# Embedded.net
KiCad netlist of a schematic drawn in EAGLE
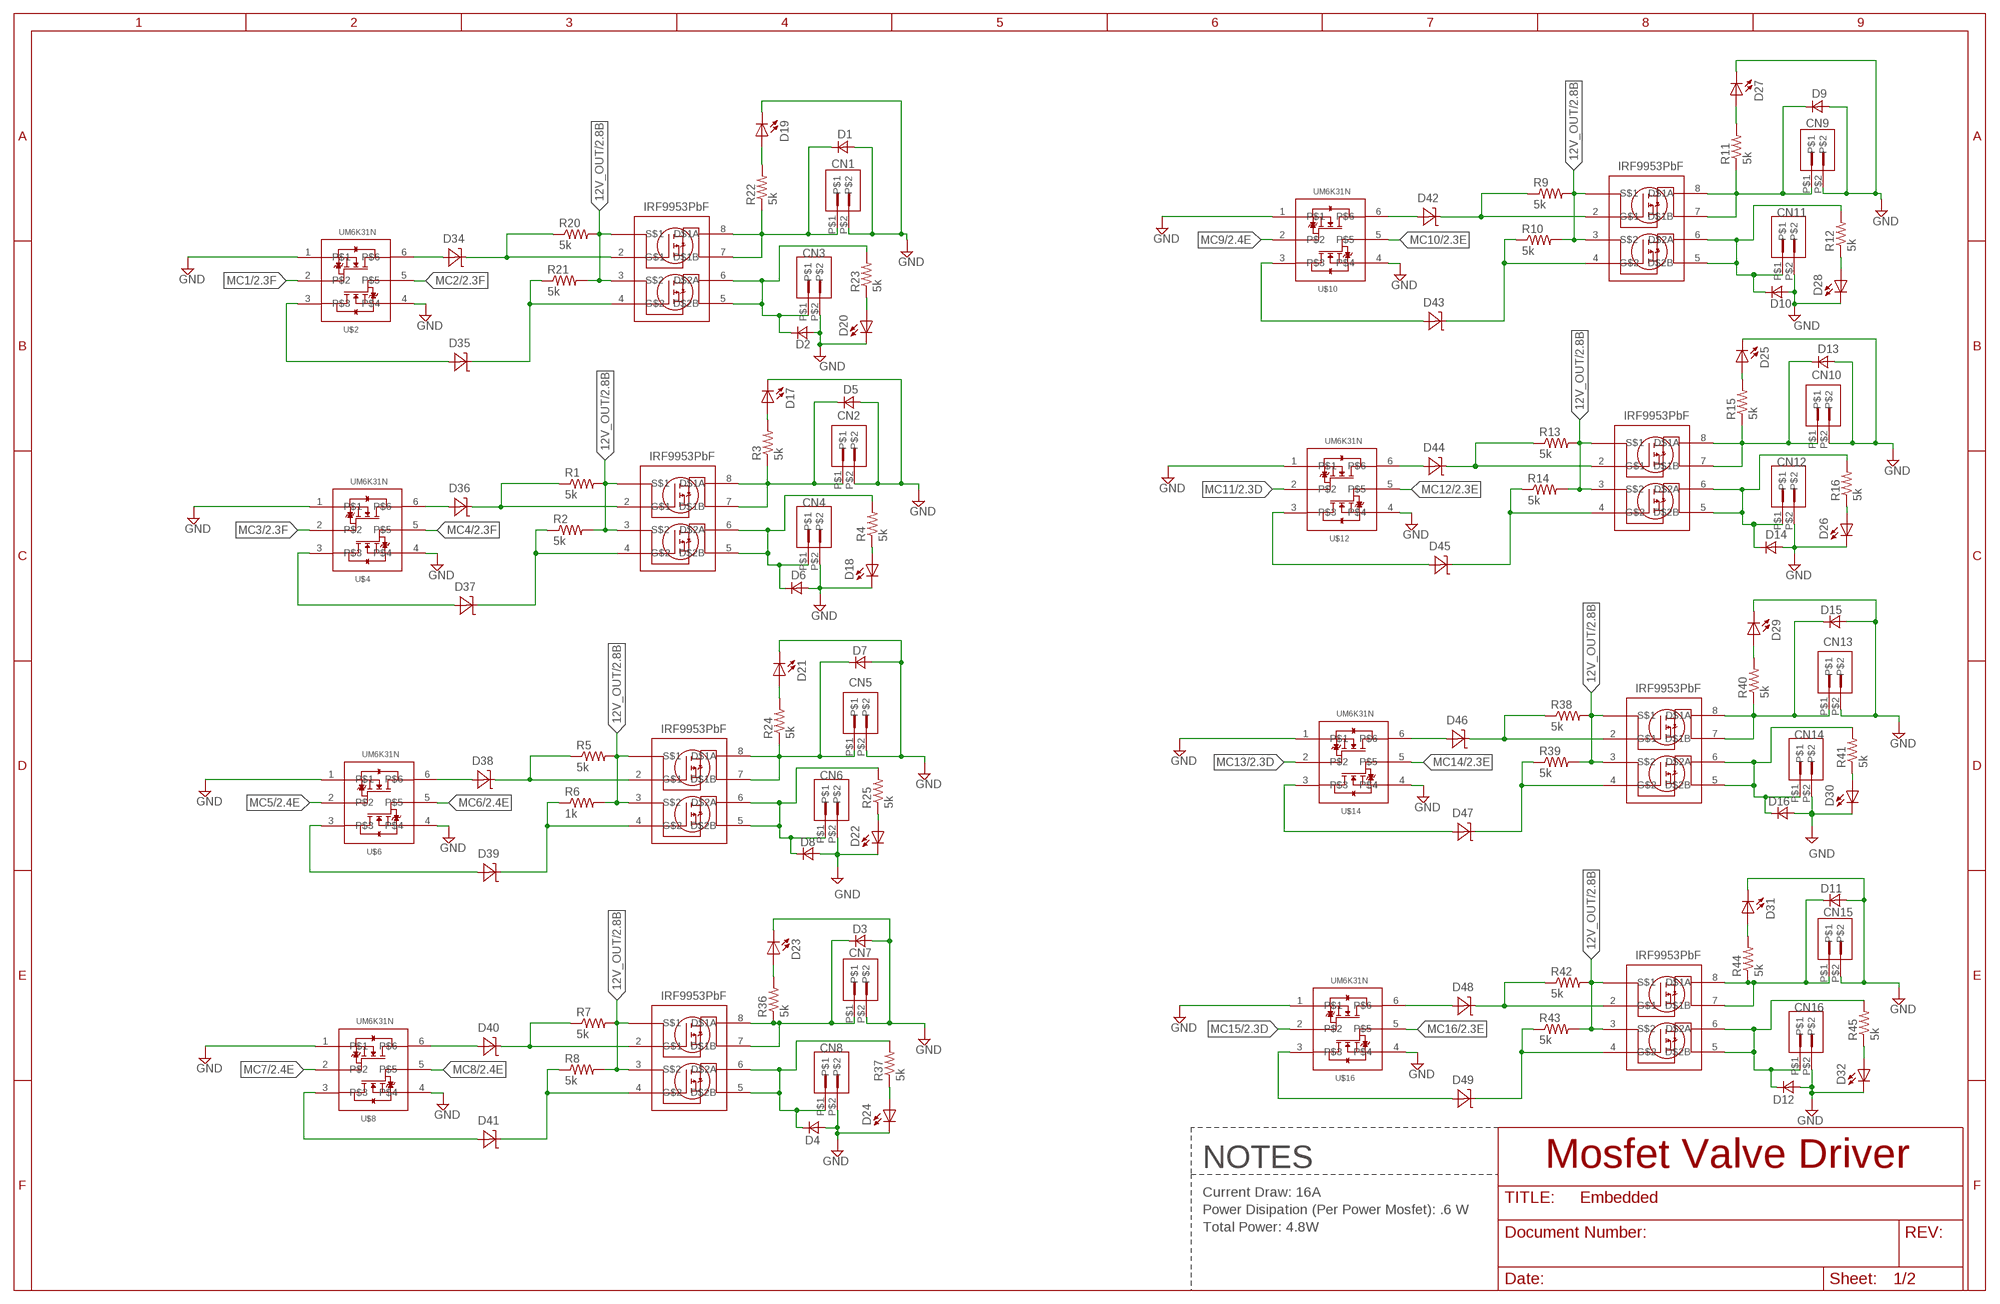
[diagram p0: schematic, sheet 1]
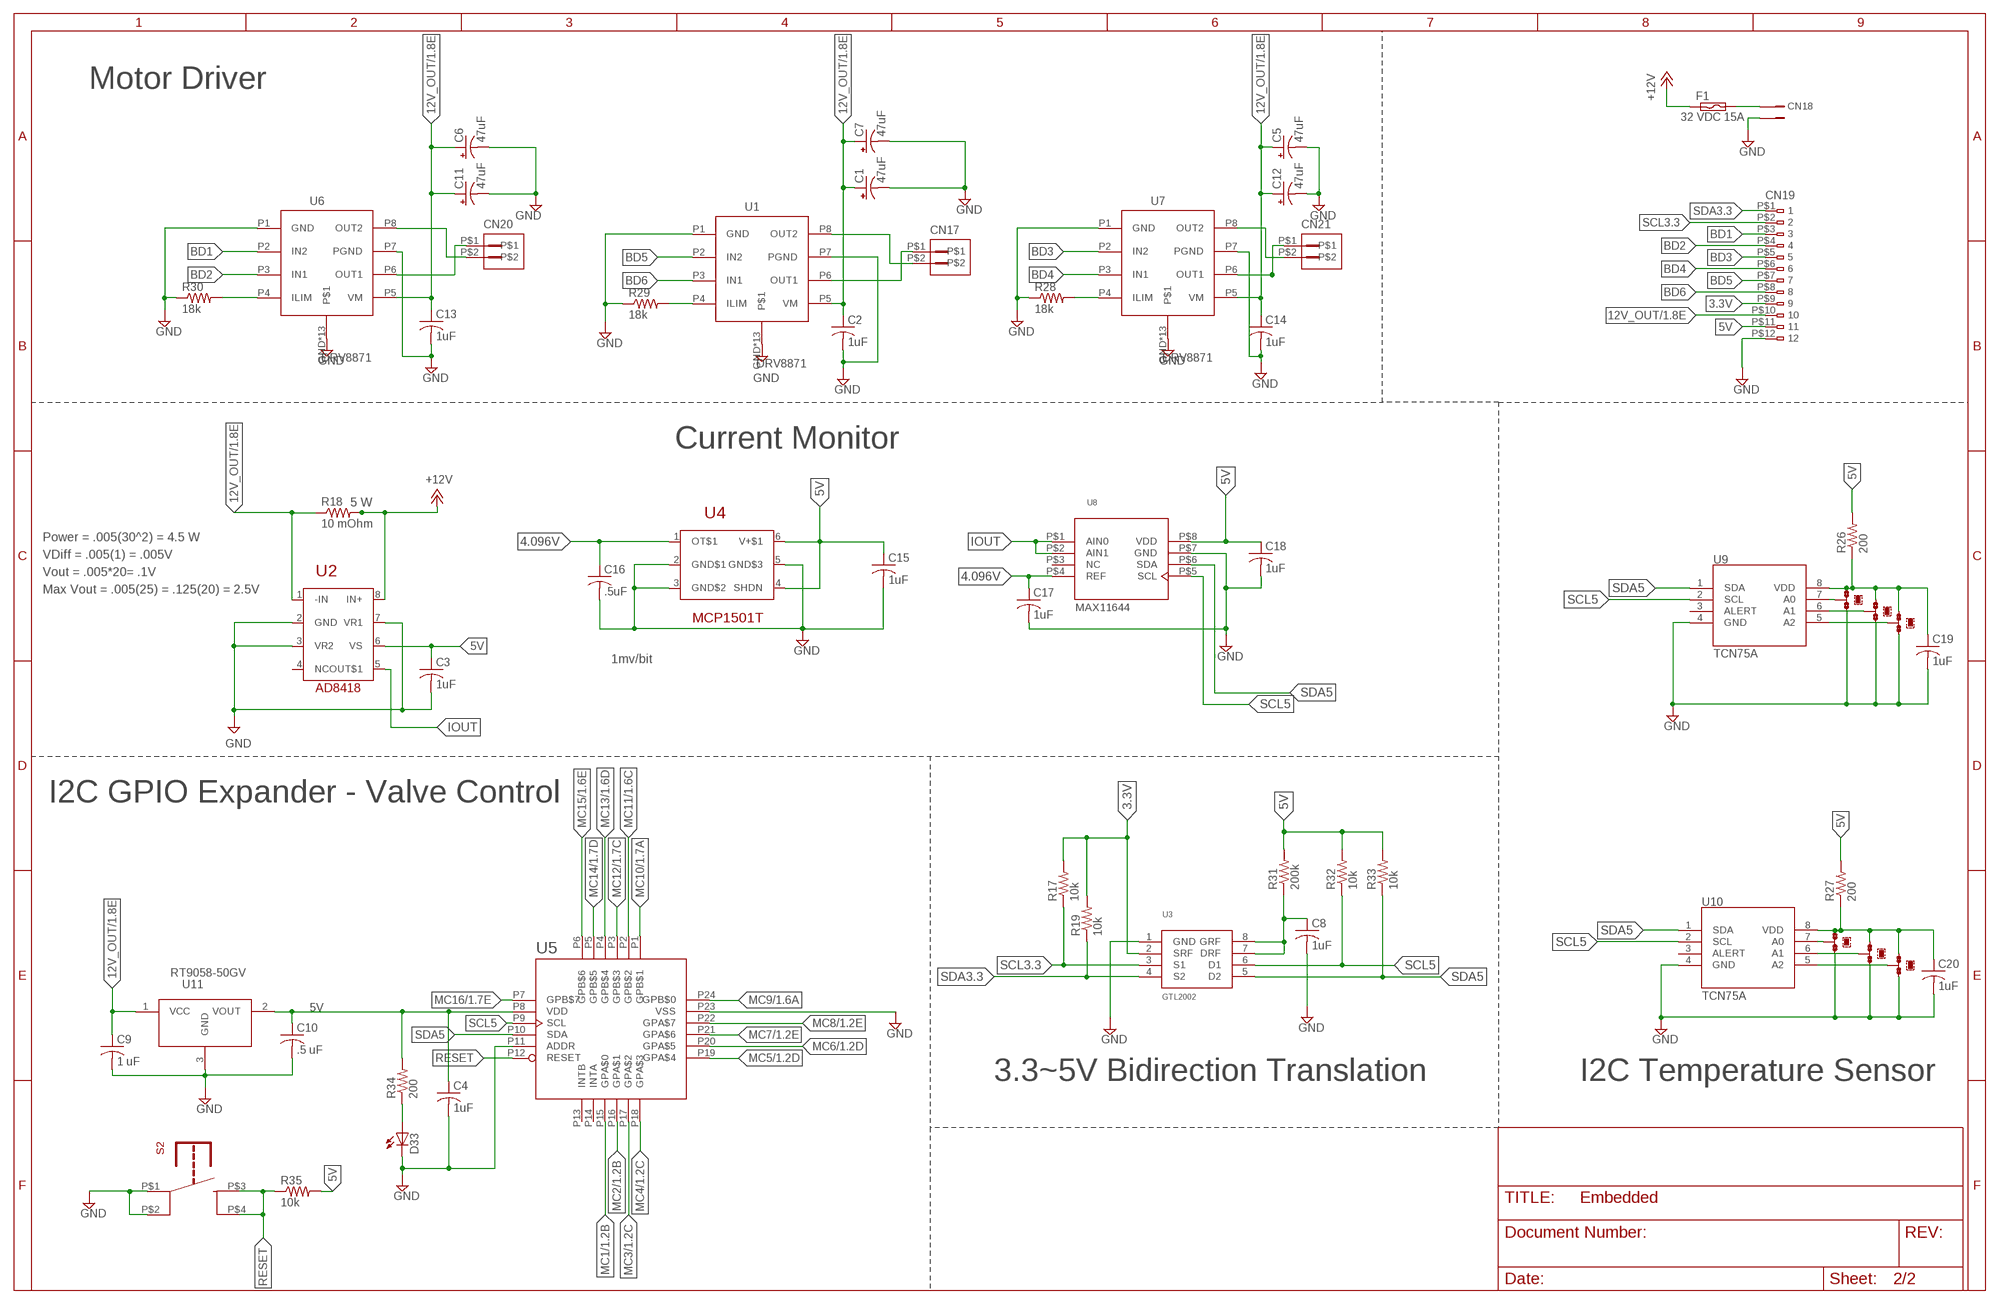
[diagram p1: schematic, sheet 2]

(export (version "E")
  (design (tool "Eeschema 10.0.6"))
  (components
    (comp (ref "CN1")
      (value "KF2510-2")
      (footprint "eagle-import:KF2540-2")
      (libsource (lib "eagle-import") (part "KF2510-2"))
    )
    (comp (ref "CN2")
      (value "KF2510-2")
      (footprint "eagle-import:KF2540-2")
      (libsource (lib "eagle-import") (part "KF2510-2"))
    )
    (comp (ref "CN3")
      (value "KF2510-2")
      (footprint "eagle-import:KF2540-2")
      (libsource (lib "eagle-import") (part "KF2510-2"))
    )
    (comp (ref "CN4")
      (value "KF2510-2")
      (footprint "eagle-import:KF2540-2")
      (libsource (lib "eagle-import") (part "KF2510-2"))
    )
    (comp (ref "CN5")
      (value "KF2510-2")
      (footprint "eagle-import:KF2540-2")
      (libsource (lib "eagle-import") (part "KF2510-2"))
    )
    (comp (ref "CN6")
      (value "KF2510-2")
      (footprint "eagle-import:KF2540-2")
      (libsource (lib "eagle-import") (part "KF2510-2"))
    )
    (comp (ref "CN7")
      (value "KF2510-2")
      (footprint "eagle-import:KF2540-2")
      (libsource (lib "eagle-import") (part "KF2510-2"))
    )
    (comp (ref "CN8")
      (value "KF2510-2")
      (footprint "eagle-import:KF2540-2")
      (libsource (lib "eagle-import") (part "KF2510-2"))
    )
    (comp (ref "CN9")
      (value "KF2510-2")
      (footprint "eagle-import:KF2540-2")
      (libsource (lib "eagle-import") (part "KF2510-2"))
    )
    (comp (ref "CN10")
      (value "KF2510-2")
      (footprint "eagle-import:KF2540-2")
      (libsource (lib "eagle-import") (part "KF2510-2"))
    )
    (comp (ref "CN11")
      (value "KF2510-2")
      (footprint "eagle-import:KF2540-2")
      (libsource (lib "eagle-import") (part "KF2510-2"))
    )
    (comp (ref "CN12")
      (value "KF2510-2")
      (footprint "eagle-import:KF2540-2")
      (libsource (lib "eagle-import") (part "KF2510-2"))
    )
    (comp (ref "CN13")
      (value "KF2510-2")
      (footprint "eagle-import:KF2540-2")
      (libsource (lib "eagle-import") (part "KF2510-2"))
    )
    (comp (ref "CN14")
      (value "KF2510-2")
      (footprint "eagle-import:KF2540-2")
      (libsource (lib "eagle-import") (part "KF2510-2"))
    )
    (comp (ref "CN15")
      (value "KF2510-2")
      (footprint "eagle-import:KF2540-2")
      (libsource (lib "eagle-import") (part "KF2510-2"))
    )
    (comp (ref "CN16")
      (value "KF2510-2")
      (footprint "eagle-import:KF2540-2")
      (libsource (lib "eagle-import") (part "KF2510-2"))
    )
    (comp (ref "D1")
      (value "RS1AL_DIODE")
      (footprint "eagle-import:DO219")
      (libsource (lib "eagle-import") (part "RS1AL_DIODE"))
    )
    (comp (ref "D2")
      (value "RS1AL_DIODE")
      (footprint "eagle-import:DO219")
      (libsource (lib "eagle-import") (part "RS1AL_DIODE"))
    )
    (comp (ref "D3")
      (value "RS1AL_DIODE")
      (footprint "eagle-import:DO219")
      (libsource (lib "eagle-import") (part "RS1AL_DIODE"))
    )
    (comp (ref "D4")
      (value "RS1AL_DIODE")
      (footprint "eagle-import:DO219")
      (libsource (lib "eagle-import") (part "RS1AL_DIODE"))
    )
    (comp (ref "D5")
      (value "RS1AL_DIODE")
      (footprint "eagle-import:DO219")
      (libsource (lib "eagle-import") (part "RS1AL_DIODE"))
    )
    (comp (ref "D6")
      (value "RS1AL_DIODE")
      (footprint "eagle-import:DO219")
      (libsource (lib "eagle-import") (part "RS1AL_DIODE"))
    )
    (comp (ref "D7")
      (value "RS1AL_DIODE")
      (footprint "eagle-import:DO219")
      (libsource (lib "eagle-import") (part "RS1AL_DIODE"))
    )
    (comp (ref "D8")
      (value "RS1AL_DIODE")
      (footprint "eagle-import:DO219")
      (libsource (lib "eagle-import") (part "RS1AL_DIODE"))
    )
    (comp (ref "D9")
      (value "RS1AL_DIODE")
      (footprint "eagle-import:DO219")
      (libsource (lib "eagle-import") (part "RS1AL_DIODE"))
    )
    (comp (ref "D10")
      (value "RS1AL_DIODE")
      (footprint "eagle-import:DO219")
      (libsource (lib "eagle-import") (part "RS1AL_DIODE"))
    )
    (comp (ref "D11")
      (value "RS1AL_DIODE")
      (footprint "eagle-import:DO219")
      (libsource (lib "eagle-import") (part "RS1AL_DIODE"))
    )
    (comp (ref "D12")
      (value "RS1AL_DIODE")
      (footprint "eagle-import:DO219")
      (libsource (lib "eagle-import") (part "RS1AL_DIODE"))
    )
    (comp (ref "D13")
      (value "RS1AL_DIODE")
      (footprint "eagle-import:DO219")
      (libsource (lib "eagle-import") (part "RS1AL_DIODE"))
    )
    (comp (ref "D14")
      (value "RS1AL_DIODE")
      (footprint "eagle-import:DO219")
      (libsource (lib "eagle-import") (part "RS1AL_DIODE"))
    )
    (comp (ref "D15")
      (value "RS1AL_DIODE")
      (footprint "eagle-import:DO219")
      (libsource (lib "eagle-import") (part "RS1AL_DIODE"))
    )
    (comp (ref "D16")
      (value "RS1AL_DIODE")
      (footprint "eagle-import:DO219")
      (libsource (lib "eagle-import") (part "RS1AL_DIODE"))
    )
    (comp (ref "D17")
      (value "1206LED")
      (footprint "eagle-import:1206")
      (libsource (lib "eagle-import") (part "1206LED"))
    )
    (comp (ref "D18")
      (value "1206LED")
      (footprint "eagle-import:1206")
      (libsource (lib "eagle-import") (part "1206LED"))
    )
    (comp (ref "D19")
      (value "1206LED")
      (footprint "eagle-import:1206")
      (libsource (lib "eagle-import") (part "1206LED"))
    )
    (comp (ref "D20")
      (value "1206LED")
      (footprint "eagle-import:1206")
      (libsource (lib "eagle-import") (part "1206LED"))
    )
    (comp (ref "D21")
      (value "1206LED")
      (footprint "eagle-import:1206")
      (libsource (lib "eagle-import") (part "1206LED"))
    )
    (comp (ref "D22")
      (value "1206LED")
      (footprint "eagle-import:1206")
      (libsource (lib "eagle-import") (part "1206LED"))
    )
    (comp (ref "D23")
      (value "1206LED")
      (footprint "eagle-import:1206")
      (libsource (lib "eagle-import") (part "1206LED"))
    )
    (comp (ref "D24")
      (value "1206LED")
      (footprint "eagle-import:1206")
      (libsource (lib "eagle-import") (part "1206LED"))
    )
    (comp (ref "D25")
      (value "1206LED")
      (footprint "eagle-import:1206")
      (libsource (lib "eagle-import") (part "1206LED"))
    )
    (comp (ref "D26")
      (value "1206LED")
      (footprint "eagle-import:1206")
      (libsource (lib "eagle-import") (part "1206LED"))
    )
    (comp (ref "D27")
      (value "1206LED")
      (footprint "eagle-import:1206")
      (libsource (lib "eagle-import") (part "1206LED"))
    )
    (comp (ref "D28")
      (value "1206LED")
      (footprint "eagle-import:1206")
      (libsource (lib "eagle-import") (part "1206LED"))
    )
    (comp (ref "D29")
      (value "1206LED")
      (footprint "eagle-import:1206")
      (libsource (lib "eagle-import") (part "1206LED"))
    )
    (comp (ref "D30")
      (value "1206LED")
      (footprint "eagle-import:1206")
      (libsource (lib "eagle-import") (part "1206LED"))
    )
    (comp (ref "D31")
      (value "1206LED")
      (footprint "eagle-import:1206")
      (libsource (lib "eagle-import") (part "1206LED"))
    )
    (comp (ref "D32")
      (value "1206LED")
      (footprint "eagle-import:1206")
      (libsource (lib "eagle-import") (part "1206LED"))
    )
    (comp (ref "D34")
      (value "6.2V")
      (footprint "eagle-import:SOD_323F")
      (libsource (lib "eagle-import") (part "MM3Z6V2B"))
    )
    (comp (ref "D35")
      (value "6.2V")
      (footprint "eagle-import:SOD_323F")
      (libsource (lib "eagle-import") (part "MM3Z6V2B"))
    )
    (comp (ref "D36")
      (value "6.2")
      (footprint "eagle-import:SOD_323F")
      (libsource (lib "eagle-import") (part "MM3Z6V2B"))
    )
    (comp (ref "D37")
      (value "6.2V")
      (footprint "eagle-import:SOD_323F")
      (libsource (lib "eagle-import") (part "MM3Z6V2B"))
    )
    (comp (ref "D38")
      (value "6.2V")
      (footprint "eagle-import:SOD_323F")
      (libsource (lib "eagle-import") (part "MM3Z6V2B"))
    )
    (comp (ref "D39")
      (value "6.2V")
      (footprint "eagle-import:SOD_323F")
      (libsource (lib "eagle-import") (part "MM3Z6V2B"))
    )
    (comp (ref "D40")
      (value "6.2V")
      (footprint "eagle-import:SOD_323F")
      (libsource (lib "eagle-import") (part "MM3Z6V2B"))
    )
    (comp (ref "D41")
      (value "6.2V")
      (footprint "eagle-import:SOD_323F")
      (libsource (lib "eagle-import") (part "MM3Z6V2B"))
    )
    (comp (ref "D42")
      (value "6.2V")
      (footprint "eagle-import:SOD_323F")
      (libsource (lib "eagle-import") (part "MM3Z6V2B"))
    )
    (comp (ref "D43")
      (value "6.2V")
      (footprint "eagle-import:SOD_323F")
      (libsource (lib "eagle-import") (part "MM3Z6V2B"))
    )
    (comp (ref "D44")
      (value "6.2V")
      (footprint "eagle-import:SOD_323F")
      (libsource (lib "eagle-import") (part "MM3Z6V2B"))
    )
    (comp (ref "D45")
      (value "6.2V")
      (footprint "eagle-import:SOD_323F")
      (libsource (lib "eagle-import") (part "MM3Z6V2B"))
    )
    (comp (ref "D46")
      (value "6.2V")
      (footprint "eagle-import:SOD_323F")
      (libsource (lib "eagle-import") (part "MM3Z6V2B"))
    )
    (comp (ref "D47")
      (value "6.2V")
      (footprint "eagle-import:SOD_323F")
      (libsource (lib "eagle-import") (part "MM3Z6V2B"))
    )
    (comp (ref "D48")
      (value "6.2V")
      (footprint "eagle-import:SOD_323F")
      (libsource (lib "eagle-import") (part "MM3Z6V2B"))
    )
    (comp (ref "D49")
      (value "6.2V")
      (footprint "eagle-import:SOD_323F")
      (libsource (lib "eagle-import") (part "MM3Z6V2B"))
    )
    (comp (ref "R1")
      (value "5k")
      (footprint "eagle-import:M0805")
      (libsource (lib "eagle-import") (part "R-US_M0805"))
    )
    (comp (ref "R2")
      (value "5k")
      (footprint "eagle-import:M0805")
      (libsource (lib "eagle-import") (part "R-US_M0805"))
    )
    (comp (ref "R3")
      (value "5k")
      (footprint "eagle-import:M0805")
      (libsource (lib "eagle-import") (part "R-US_M0805"))
    )
    (comp (ref "R4")
      (value "5k")
      (footprint "eagle-import:M0805")
      (libsource (lib "eagle-import") (part "R-US_M0805"))
    )
    (comp (ref "R5")
      (value "5k")
      (footprint "eagle-import:M0805")
      (libsource (lib "eagle-import") (part "R-US_M0805"))
    )
    (comp (ref "R6")
      (value "1k")
      (footprint "eagle-import:M0805")
      (libsource (lib "eagle-import") (part "R-US_M0805"))
    )
    (comp (ref "R7")
      (value "5k")
      (footprint "eagle-import:M0805")
      (libsource (lib "eagle-import") (part "R-US_M0805"))
    )
    (comp (ref "R8")
      (value "5k")
      (footprint "eagle-import:M0805")
      (libsource (lib "eagle-import") (part "R-US_M0805"))
    )
    (comp (ref "R9")
      (value "5k")
      (footprint "eagle-import:M0805")
      (libsource (lib "eagle-import") (part "R-US_M0805"))
    )
    (comp (ref "R10")
      (value "5k")
      (footprint "eagle-import:M0805")
      (libsource (lib "eagle-import") (part "R-US_M0805"))
    )
    (comp (ref "R11")
      (value "5k")
      (footprint "eagle-import:M0805")
      (libsource (lib "eagle-import") (part "R-US_M0805"))
    )
    (comp (ref "R12")
      (value "5k")
      (footprint "eagle-import:M0805")
      (libsource (lib "eagle-import") (part "R-US_M0805"))
    )
    (comp (ref "R13")
      (value "5k")
      (footprint "eagle-import:M0805")
      (libsource (lib "eagle-import") (part "R-US_M0805"))
    )
    (comp (ref "R14")
      (value "5k")
      (footprint "eagle-import:M0805")
      (libsource (lib "eagle-import") (part "R-US_M0805"))
    )
    (comp (ref "R15")
      (value "5k")
      (footprint "eagle-import:M0805")
      (libsource (lib "eagle-import") (part "R-US_M0805"))
    )
    (comp (ref "R16")
      (value "5k")
      (footprint "eagle-import:M0805")
      (libsource (lib "eagle-import") (part "R-US_M0805"))
    )
    (comp (ref "R20")
      (value "5k")
      (footprint "eagle-import:M0805")
      (libsource (lib "eagle-import") (part "R-US_M0805"))
    )
    (comp (ref "R21")
      (value "5k")
      (footprint "eagle-import:M0805")
      (libsource (lib "eagle-import") (part "R-US_M0805"))
    )
    (comp (ref "R22")
      (value "5k")
      (footprint "eagle-import:M0805")
      (libsource (lib "eagle-import") (part "R-US_M0805"))
    )
    (comp (ref "R23")
      (value "5k")
      (footprint "eagle-import:M0805")
      (libsource (lib "eagle-import") (part "R-US_M0805"))
    )
    (comp (ref "R24")
      (value "5k")
      (footprint "eagle-import:M0805")
      (libsource (lib "eagle-import") (part "R-US_M0805"))
    )
    (comp (ref "R25")
      (value "5k")
      (footprint "eagle-import:M0805")
      (libsource (lib "eagle-import") (part "R-US_M0805"))
    )
    (comp (ref "R36")
      (value "5k")
      (footprint "eagle-import:M0805")
      (libsource (lib "eagle-import") (part "R-US_M0805"))
    )
    (comp (ref "R37")
      (value "5k")
      (footprint "eagle-import:M0805")
      (libsource (lib "eagle-import") (part "R-US_M0805"))
    )
    (comp (ref "R38")
      (value "5k")
      (footprint "eagle-import:M0805")
      (libsource (lib "eagle-import") (part "R-US_M0805"))
    )
    (comp (ref "R39")
      (value "5k")
      (footprint "eagle-import:M0805")
      (libsource (lib "eagle-import") (part "R-US_M0805"))
    )
    (comp (ref "R40")
      (value "5k")
      (footprint "eagle-import:M0805")
      (libsource (lib "eagle-import") (part "R-US_M0805"))
    )
    (comp (ref "R41")
      (value "5k")
      (footprint "eagle-import:M0805")
      (libsource (lib "eagle-import") (part "R-US_M0805"))
    )
    (comp (ref "R42")
      (value "5k")
      (footprint "eagle-import:M0805")
      (libsource (lib "eagle-import") (part "R-US_M0805"))
    )
    (comp (ref "R43")
      (value "5k")
      (footprint "eagle-import:M0805")
      (libsource (lib "eagle-import") (part "R-US_M0805"))
    )
    (comp (ref "R44")
      (value "5k")
      (footprint "eagle-import:M0805")
      (libsource (lib "eagle-import") (part "R-US_M0805"))
    )
    (comp (ref "R45")
      (value "5k")
      (footprint "eagle-import:M0805")
      (libsource (lib "eagle-import") (part "R-US_M0805"))
    )
    (comp (ref "U$1")
      (value "IRF9953PBF")
      (footprint "eagle-import:SO-8")
      (libsource (lib "eagle-import") (part "IRF9953PBF"))
    )
    (comp (ref "U$2")
      (value "UM6K31N")
      (footprint "eagle-import:UMT6")
      (libsource (lib "eagle-import") (part "UM6K31N"))
    )
    (comp (ref "U$3")
      (value "IRF9953PBF")
      (footprint "eagle-import:SO-8")
      (libsource (lib "eagle-import") (part "IRF9953PBF"))
    )
    (comp (ref "U$4")
      (value "UM6K31N")
      (footprint "eagle-import:UMT6")
      (libsource (lib "eagle-import") (part "UM6K31N"))
    )
    (comp (ref "U$5")
      (value "IRF9953PBF")
      (footprint "eagle-import:SO-8")
      (libsource (lib "eagle-import") (part "IRF9953PBF"))
    )
    (comp (ref "U$6")
      (value "UM6K31N")
      (footprint "eagle-import:UMT6")
      (libsource (lib "eagle-import") (part "UM6K31N"))
    )
    (comp (ref "U$7")
      (value "IRF9953PBF")
      (footprint "eagle-import:SO-8")
      (libsource (lib "eagle-import") (part "IRF9953PBF"))
    )
    (comp (ref "U$8")
      (value "UM6K31N")
      (footprint "eagle-import:UMT6")
      (libsource (lib "eagle-import") (part "UM6K31N"))
    )
    (comp (ref "U$9")
      (value "IRF9953PBF")
      (footprint "eagle-import:SO-8")
      (libsource (lib "eagle-import") (part "IRF9953PBF"))
    )
    (comp (ref "U$10")
      (value "UM6K31N")
      (footprint "eagle-import:UMT6")
      (libsource (lib "eagle-import") (part "UM6K31N"))
    )
    (comp (ref "U$11")
      (value "IRF9953PBF")
      (footprint "eagle-import:SO-8")
      (libsource (lib "eagle-import") (part "IRF9953PBF"))
    )
    (comp (ref "U$12")
      (value "UM6K31N")
      (footprint "eagle-import:UMT6")
      (libsource (lib "eagle-import") (part "UM6K31N"))
    )
    (comp (ref "U$13")
      (value "IRF9953PBF")
      (footprint "eagle-import:SO-8")
      (libsource (lib "eagle-import") (part "IRF9953PBF"))
    )
    (comp (ref "U$14")
      (value "UM6K31N")
      (footprint "eagle-import:UMT6")
      (libsource (lib "eagle-import") (part "UM6K31N"))
    )
    (comp (ref "U$15")
      (value "IRF9953PBF")
      (footprint "eagle-import:SO-8")
      (libsource (lib "eagle-import") (part "IRF9953PBF"))
    )
    (comp (ref "U$16")
      (value "UM6K31N")
      (footprint "eagle-import:UMT6")
      (libsource (lib "eagle-import") (part "UM6K31N"))
    )
    (comp (ref "C1")
      (value "47uF")
      (footprint "eagle-import:UD-6,3X7,7_NICHICON")
      (libsource (lib "eagle-import") (part "CPOL-USUD-6,3X7,7"))
    )
    (comp (ref "C2")
      (value "1uF")
      (footprint "eagle-import:C1206")
      (libsource (lib "eagle-import") (part "C-USC1206"))
    )
    (comp (ref "C3")
      (value "1uF")
      (footprint "eagle-import:C1206")
      (libsource (lib "eagle-import") (part "C-USC1206"))
    )
    (comp (ref "C4")
      (value "1uF")
      (footprint "eagle-import:C1206")
      (libsource (lib "eagle-import") (part "C-USC1206"))
    )
    (comp (ref "C5")
      (value "47uF")
      (footprint "eagle-import:UD-6,3X7,7_NICHICON")
      (libsource (lib "eagle-import") (part "CPOL-USUD-6,3X7,7"))
    )
    (comp (ref "C6")
      (value "47uF")
      (footprint "eagle-import:UD-6,3X7,7_NICHICON")
      (libsource (lib "eagle-import") (part "CPOL-USUD-6,3X7,7"))
    )
    (comp (ref "C7")
      (value "47uF")
      (footprint "eagle-import:UD-6,3X7,7_NICHICON")
      (libsource (lib "eagle-import") (part "CPOL-USUD-6,3X7,7"))
    )
    (comp (ref "C8")
      (value "1uF")
      (footprint "eagle-import:C1206")
      (libsource (lib "eagle-import") (part "C-USC1206"))
    )
    (comp (ref "C9")
      (value "1 uF")
      (footprint "eagle-import:C1206")
      (libsource (lib "eagle-import") (part "resistor_348_C-USC1206"))
    )
    (comp (ref "C10")
      (value ".5 uF")
      (footprint "eagle-import:C1206")
      (libsource (lib "eagle-import") (part "resistor_348_C-USC1206"))
    )
    (comp (ref "C11")
      (value "47uF")
      (footprint "eagle-import:UD-6,3X7,7_NICHICON")
      (libsource (lib "eagle-import") (part "CPOL-USUD-6,3X7,7"))
    )
    (comp (ref "C12")
      (value "47uF")
      (footprint "eagle-import:UD-6,3X7,7_NICHICON")
      (libsource (lib "eagle-import") (part "CPOL-USUD-6,3X7,7"))
    )
    (comp (ref "C13")
      (value "1uF")
      (footprint "eagle-import:C1206")
      (libsource (lib "eagle-import") (part "C-USC1206"))
    )
    (comp (ref "C14")
      (value "1uF")
      (footprint "eagle-import:C1206")
      (libsource (lib "eagle-import") (part "C-USC1206"))
    )
    (comp (ref "C15")
      (value "1uF")
      (footprint "eagle-import:C1206")
      (libsource (lib "eagle-import") (part "C-USC1206"))
    )
    (comp (ref "C16")
      (value ".5uF")
      (footprint "eagle-import:C1206")
      (libsource (lib "eagle-import") (part "C-USC1206"))
    )
    (comp (ref "C17")
      (value "1uF")
      (footprint "eagle-import:C1206")
      (libsource (lib "eagle-import") (part "C-USC1206"))
    )
    (comp (ref "C18")
      (value "1uF")
      (footprint "eagle-import:C1206")
      (libsource (lib "eagle-import") (part "C-USC1206"))
    )
    (comp (ref "C19")
      (value "1uF")
      (footprint "eagle-import:C1206")
      (libsource (lib "eagle-import") (part "C-USC1206"))
    )
    (comp (ref "C20")
      (value "1uF")
      (footprint "eagle-import:C1206")
      (libsource (lib "eagle-import") (part "C-USC1206"))
    )
    (comp (ref "CN17")
      (value "KF2510-2")
      (footprint "eagle-import:KF2540-2")
      (libsource (lib "eagle-import") (part "KF2510-2"))
    )
    (comp (ref "CN18")
      (value "PHEON_MKDS_CON")
      (footprint "eagle-import:PHOEN_MKDS")
      (libsource (lib "eagle-import") (part "PHEON_MKDS_CON"))
    )
    (comp (ref "CN19")
      (value "MOLEX_FPC_52892_1233")
      (footprint "eagle-import:MOLEX_WM1108")
      (libsource (lib "eagle-import") (part "MOLEX_FPC_52892_1233"))
    )
    (comp (ref "CN20")
      (value "KF2510-2")
      (footprint "eagle-import:KF2540-2")
      (libsource (lib "eagle-import") (part "KF2510-2"))
    )
    (comp (ref "CN21")
      (value "KF2510-2")
      (footprint "eagle-import:KF2540-2")
      (libsource (lib "eagle-import") (part "KF2510-2"))
    )
    (comp (ref "D33")
      (value "1206LED")
      (footprint "eagle-import:1206")
      (libsource (lib "eagle-import") (part "1206LED"))
    )
    (comp (ref "F1")
      (value "32 VDC 15A")
      (footprint "eagle-import:LITTLEFUSE125_003")
      (libsource (lib "eagle-import") (part "LITTLEFUSE_AGU"))
    )
    (comp (ref "JMP1")
      (value "0R-JUMPA")
      (footprint "eagle-import:A0R-JMP")
      (libsource (lib "eagle-import") (part "0R-JUMPA"))
    )
    (comp (ref "JMP2")
      (value "0R-JUMPA")
      (footprint "eagle-import:A0R-JMP")
      (libsource (lib "eagle-import") (part "0R-JUMPA"))
    )
    (comp (ref "JMP3")
      (value "0R-JUMPA")
      (footprint "eagle-import:A0R-JMP")
      (libsource (lib "eagle-import") (part "0R-JUMPA"))
    )
    (comp (ref "JMP4")
      (value "0R-JUMPA")
      (footprint "eagle-import:A0R-JMP")
      (libsource (lib "eagle-import") (part "0R-JUMPA"))
    )
    (comp (ref "JMP5")
      (value "0R-JUMPA")
      (footprint "eagle-import:A0R-JMP")
      (libsource (lib "eagle-import") (part "0R-JUMPA"))
    )
    (comp (ref "JMP6")
      (value "0R-JUMPA")
      (footprint "eagle-import:A0R-JMP")
      (libsource (lib "eagle-import") (part "0R-JUMPA"))
    )
    (comp (ref "R17")
      (value "10k")
      (footprint "eagle-import:M0805")
      (libsource (lib "eagle-import") (part "R-US_M0805"))
    )
    (comp (ref "R18")
      (value "10 mOhm")
      (footprint "eagle-import:2818")
      (libsource (lib "eagle-import") (part "WSHM2818"))
    )
    (comp (ref "R19")
      (value "10k")
      (footprint "eagle-import:M0805")
      (libsource (lib "eagle-import") (part "R-US_M0805"))
    )
    (comp (ref "R26")
      (value "200")
      (footprint "eagle-import:M0805")
      (libsource (lib "eagle-import") (part "R-US_M0805"))
    )
    (comp (ref "R27")
      (value "200")
      (footprint "eagle-import:M0805")
      (libsource (lib "eagle-import") (part "R-US_M0805"))
    )
    (comp (ref "R28")
      (value "18k")
      (footprint "eagle-import:M0805")
      (libsource (lib "eagle-import") (part "R-US_M0805"))
    )
    (comp (ref "R29")
      (value "18k")
      (footprint "eagle-import:M0805")
      (libsource (lib "eagle-import") (part "R-US_M0805"))
    )
    (comp (ref "R30")
      (value "18k")
      (footprint "eagle-import:M0805")
      (libsource (lib "eagle-import") (part "R-US_M0805"))
    )
    (comp (ref "R31")
      (value "200k")
      (footprint "eagle-import:M0805")
      (libsource (lib "eagle-import") (part "R-US_M0805"))
    )
    (comp (ref "R32")
      (value "10k")
      (footprint "eagle-import:M0805")
      (libsource (lib "eagle-import") (part "R-US_M0805"))
    )
    (comp (ref "R33")
      (value "10k")
      (footprint "eagle-import:M0805")
      (libsource (lib "eagle-import") (part "R-US_M0805"))
    )
    (comp (ref "R34")
      (value "200")
      (footprint "eagle-import:M0805")
      (libsource (lib "eagle-import") (part "R-US_M0805"))
    )
    (comp (ref "R35")
      (value "10k")
      (footprint "eagle-import:M0805")
      (libsource (lib "eagle-import") (part "R-US_M0805"))
    )
    (comp (ref "S2")
      (value "TL3305")
      (footprint "eagle-import:TL3305")
      (libsource (lib "eagle-import") (part "TL3305"))
    )
    (comp (ref "U1")
      (value "DRV8871")
      (footprint "eagle-import:SO8_EP")
      (libsource (lib "eagle-import") (part "DRV8871"))
    )
    (comp (ref "U2")
      (value "AD8418BZR")
      (footprint "eagle-import:DGK_S-PDSO-G8")
      (libsource (lib "eagle-import") (part "AD8418BZR"))
    )
    (comp (ref "U3")
      (value "GTL2002")
      (footprint "eagle-import:SO-8")
      (libsource (lib "eagle-import") (part "GTL2002"))
    )
    (comp (ref "U4")
      (value "MCP1501T-40E/CHY")
      (footprint "eagle-import:SOT23-6")
      (libsource (lib "eagle-import") (part "MCP1501T-40E/CHY"))
    )
    (comp (ref "U5")
      (value "MCP23018")
      (footprint "eagle-import:QFN_24_EP")
      (libsource (lib "eagle-import") (part "MCP23018"))
    )
    (comp (ref "U6")
      (value "DRV8871")
      (footprint "eagle-import:SO8_EP")
      (libsource (lib "eagle-import") (part "DRV8871"))
    )
    (comp (ref "U7")
      (value "DRV8871")
      (footprint "eagle-import:SO8_EP")
      (libsource (lib "eagle-import") (part "DRV8871"))
    )
    (comp (ref "U8")
      (value "MAX11645UMAX8")
      (footprint "eagle-import:UMAX8")
      (libsource (lib "eagle-import") (part "MAX11645UMAX8"))
    )
    (comp (ref "U9")
      (value "TCN75A")
      (footprint "eagle-import:DGK_S-PDSO-G8")
      (libsource (lib "eagle-import") (part "TCN75A"))
    )
    (comp (ref "U10")
      (value "TCN75A")
      (footprint "eagle-import:DGK_S-PDSO-G8")
      (libsource (lib "eagle-import") (part "TCN75A"))
    )
    (comp (ref "U11")
      (value "RT9058-50GV")
      (footprint "eagle-import:SOT23")
      (libsource (lib "eagle-import") (part "RT9058-50GV"))
    )
  )
  (nets
    (net (code "1") (name "+12V") (class "Default")
      (node (ref "F1") (pin "P$1") (pinfunction "1_P$1") (pintype "passive"))
      (node (ref "R18") (pin "P$2") (pinfunction "2_P$2") (pintype "passive"))
      (node (ref "U2") (pin "8") (pinfunction "IN+_8") (pintype "bidirectional"))
    )
    (net (code "2") (name "3.3V") (class "Default")
      (node (ref "CN19") (pin "P$9") (pinfunction "9_P$9") (pintype "passive"))
      (node (ref "R17") (pin "2") (pinfunction "2_2") (pintype "passive"))
      (node (ref "R19") (pin "2") (pinfunction "2_2") (pintype "passive"))
      (node (ref "U3") (pin "2") (pinfunction "SRF_2") (pintype "power_in"))
    )
    (net (code "3") (name "4.096V") (class "Default")
      (node (ref "C16") (pin "1") (pinfunction "1_1") (pintype "passive"))
      (node (ref "C17") (pin "1") (pinfunction "1_1") (pintype "passive"))
      (node (ref "U4") (pin "1") (pinfunction "OT$1_1") (pintype "output"))
      (node (ref "U8") (pin "P$4") (pinfunction "REF_P$4") (pintype "input"))
    )
    (net (code "4") (name "5V") (class "Default")
      (node (ref "C10") (pin "1") (pinfunction "1_1") (pintype "passive"))
      (node (ref "C15") (pin "1") (pinfunction "1_1") (pintype "passive"))
      (node (ref "C18") (pin "1") (pinfunction "1_1") (pintype "passive"))
      (node (ref "C3") (pin "1") (pinfunction "1_1") (pintype "passive"))
      (node (ref "C4") (pin "1") (pinfunction "1_1") (pintype "passive"))
      (node (ref "CN19") (pin "P$11") (pinfunction "11_P$11") (pintype "passive"))
      (node (ref "R26") (pin "2") (pinfunction "2_2") (pintype "passive"))
      (node (ref "R27") (pin "2") (pinfunction "2_2") (pintype "passive"))
      (node (ref "R31") (pin "2") (pinfunction "2_2") (pintype "passive"))
      (node (ref "R32") (pin "2") (pinfunction "2_2") (pintype "passive"))
      (node (ref "R33") (pin "2") (pinfunction "2_2") (pintype "passive"))
      (node (ref "R34") (pin "2") (pinfunction "2_2") (pintype "passive"))
      (node (ref "R35") (pin "2") (pinfunction "2_2") (pintype "passive"))
      (node (ref "U11") (pin "2") (pinfunction "VOUT_2") (pintype "bidirectional"))
      (node (ref "U2") (pin "6") (pinfunction "VS_6") (pintype "power_in"))
      (node (ref "U4") (pin "4") (pinfunction "SHDN_4") (pintype "bidirectional"))
      (node (ref "U4") (pin "6") (pinfunction "V+$1_6") (pintype "power_in"))
      (node (ref "U5") (pin "P8") (pinfunction "VDD_P8") (pintype "power_in"))
      (node (ref "U8") (pin "P$8") (pinfunction "VDD_P$8") (pintype "power_in"))
    )
    (net (code "5") (name "12V_OUT") (class "Default")
      (node (ref "C1") (pin "+") (pinfunction "+_+") (pintype "passive"))
      (node (ref "C11") (pin "+") (pinfunction "+_+") (pintype "passive"))
      (node (ref "C12") (pin "+") (pinfunction "+_+") (pintype "passive"))
      (node (ref "C13") (pin "1") (pinfunction "1_1") (pintype "passive"))
      (node (ref "C14") (pin "1") (pinfunction "1_1") (pintype "passive"))
      (node (ref "C2") (pin "1") (pinfunction "1_1") (pintype "passive"))
      (node (ref "C5") (pin "+") (pinfunction "+_+") (pintype "passive"))
      (node (ref "C6") (pin "+") (pinfunction "+_+") (pintype "passive"))
      (node (ref "C7") (pin "+") (pinfunction "+_+") (pintype "passive"))
      (node (ref "C9") (pin "1") (pinfunction "1_1") (pintype "passive"))
      (node (ref "CN19") (pin "P$10") (pinfunction "10_P$10") (pintype "passive"))
      (node (ref "R1") (pin "2") (pinfunction "2_2") (pintype "passive"))
      (node (ref "R10") (pin "2") (pinfunction "2_2") (pintype "passive"))
      (node (ref "R13") (pin "2") (pinfunction "2_2") (pintype "passive"))
      (node (ref "R14") (pin "2") (pinfunction "2_2") (pintype "passive"))
      (node (ref "R18") (pin "P$1") (pinfunction "1_P$1") (pintype "passive"))
      (node (ref "R2") (pin "2") (pinfunction "2_2") (pintype "passive"))
      (node (ref "R20") (pin "2") (pinfunction "2_2") (pintype "passive"))
      (node (ref "R21") (pin "2") (pinfunction "2_2") (pintype "passive"))
      (node (ref "R38") (pin "2") (pinfunction "2_2") (pintype "passive"))
      (node (ref "R39") (pin "2") (pinfunction "2_2") (pintype "passive"))
      (node (ref "R42") (pin "2") (pinfunction "2_2") (pintype "passive"))
      (node (ref "R43") (pin "2") (pinfunction "2_2") (pintype "passive"))
      (node (ref "R5") (pin "2") (pinfunction "2_2") (pintype "passive"))
      (node (ref "R6") (pin "2") (pinfunction "2_2") (pintype "passive"))
      (node (ref "R7") (pin "2") (pinfunction "2_2") (pintype "passive"))
      (node (ref "R8") (pin "2") (pinfunction "2_2") (pintype "passive"))
      (node (ref "R9") (pin "2") (pinfunction "2_2") (pintype "passive"))
      (node (ref "U$1") (pin "1") (pinfunction "S$1_1") (pintype "bidirectional"))
      (node (ref "U$1") (pin "3") (pinfunction "S$2_3") (pintype "bidirectional"))
      (node (ref "U$11") (pin "1") (pinfunction "S$1_1") (pintype "bidirectional"))
      (node (ref "U$11") (pin "3") (pinfunction "S$2_3") (pintype "bidirectional"))
      (node (ref "U$13") (pin "1") (pinfunction "S$1_1") (pintype "bidirectional"))
      (node (ref "U$13") (pin "3") (pinfunction "S$2_3") (pintype "bidirectional"))
      (node (ref "U$15") (pin "1") (pinfunction "S$1_1") (pintype "bidirectional"))
      (node (ref "U$15") (pin "3") (pinfunction "S$2_3") (pintype "bidirectional"))
      (node (ref "U$3") (pin "1") (pinfunction "S$1_1") (pintype "bidirectional"))
      (node (ref "U$3") (pin "3") (pinfunction "S$2_3") (pintype "bidirectional"))
      (node (ref "U$5") (pin "1") (pinfunction "S$1_1") (pintype "bidirectional"))
      (node (ref "U$5") (pin "3") (pinfunction "S$2_3") (pintype "bidirectional"))
      (node (ref "U$7") (pin "1") (pinfunction "S$1_1") (pintype "bidirectional"))
      (node (ref "U$7") (pin "3") (pinfunction "S$2_3") (pintype "bidirectional"))
      (node (ref "U$9") (pin "1") (pinfunction "S$1_1") (pintype "bidirectional"))
      (node (ref "U$9") (pin "3") (pinfunction "S$2_3") (pintype "bidirectional"))
      (node (ref "U1") (pin "P5") (pinfunction "VM_P5") (pintype "power_in"))
      (node (ref "U11") (pin "1") (pinfunction "VCC_1") (pintype "bidirectional"))
      (node (ref "U2") (pin "1") (pinfunction "-IN_1") (pintype "bidirectional"))
      (node (ref "U6") (pin "P5") (pinfunction "VM_P5") (pintype "power_in"))
      (node (ref "U7") (pin "P5") (pinfunction "VM_P5") (pintype "power_in"))
    )
    (net (code "6") (name "BD1") (class "Default")
      (node (ref "CN19") (pin "P$3") (pinfunction "3_P$3") (pintype "passive"))
      (node (ref "U6") (pin "P2") (pinfunction "IN2_P2") (pintype "input"))
    )
    (net (code "7") (name "BD2") (class "Default")
      (node (ref "CN19") (pin "P$4") (pinfunction "4_P$4") (pintype "passive"))
      (node (ref "U6") (pin "P3") (pinfunction "IN1_P3") (pintype "input"))
    )
    (net (code "8") (name "BD3") (class "Default")
      (node (ref "CN19") (pin "P$5") (pinfunction "5_P$5") (pintype "passive"))
      (node (ref "U7") (pin "P2") (pinfunction "IN2_P2") (pintype "input"))
    )
    (net (code "9") (name "BD4") (class "Default")
      (node (ref "CN19") (pin "P$6") (pinfunction "6_P$6") (pintype "passive"))
      (node (ref "U7") (pin "P3") (pinfunction "IN1_P3") (pintype "input"))
    )
    (net (code "10") (name "BD5") (class "Default")
      (node (ref "CN19") (pin "P$7") (pinfunction "7_P$7") (pintype "passive"))
      (node (ref "U1") (pin "P2") (pinfunction "IN2_P2") (pintype "input"))
    )
    (net (code "11") (name "BD6") (class "Default")
      (node (ref "CN19") (pin "P$8") (pinfunction "8_P$8") (pintype "passive"))
      (node (ref "U1") (pin "P3") (pinfunction "IN1_P3") (pintype "input"))
    )
    (net (code "12") (name "GND") (class "Default")
      (node (ref "C1") (pin "-") (pinfunction "-_-") (pintype "passive"))
      (node (ref "C10") (pin "2") (pinfunction "2_2") (pintype "passive"))
      (node (ref "C11") (pin "-") (pinfunction "-_-") (pintype "passive"))
      (node (ref "C12") (pin "-") (pinfunction "-_-") (pintype "passive"))
      (node (ref "C13") (pin "2") (pinfunction "2_2") (pintype "passive"))
      (node (ref "C14") (pin "2") (pinfunction "2_2") (pintype "passive"))
      (node (ref "C15") (pin "2") (pinfunction "2_2") (pintype "passive"))
      (node (ref "C16") (pin "2") (pinfunction "2_2") (pintype "passive"))
      (node (ref "C17") (pin "2") (pinfunction "2_2") (pintype "passive"))
      (node (ref "C18") (pin "2") (pinfunction "2_2") (pintype "passive"))
      (node (ref "C19") (pin "2") (pinfunction "2_2") (pintype "passive"))
      (node (ref "C2") (pin "2") (pinfunction "2_2") (pintype "passive"))
      (node (ref "C20") (pin "2") (pinfunction "2_2") (pintype "passive"))
      (node (ref "C3") (pin "2") (pinfunction "2_2") (pintype "passive"))
      (node (ref "C4") (pin "2") (pinfunction "2_2") (pintype "passive"))
      (node (ref "C5") (pin "-") (pinfunction "-_-") (pintype "passive"))
      (node (ref "C6") (pin "-") (pinfunction "-_-") (pintype "passive"))
      (node (ref "C7") (pin "-") (pinfunction "-_-") (pintype "passive"))
      (node (ref "C8") (pin "2") (pinfunction "2_2") (pintype "passive"))
      (node (ref "C9") (pin "2") (pinfunction "2_2") (pintype "passive"))
      (node (ref "CN1") (pin "P$2") (pinfunction "P$2_P$2") (pintype "bidirectional"))
      (node (ref "CN10") (pin "P$2") (pinfunction "P$2_P$2") (pintype "bidirectional"))
      (node (ref "CN11") (pin "P$2") (pinfunction "P$2_P$2") (pintype "bidirectional"))
      (node (ref "CN12") (pin "P$2") (pinfunction "P$2_P$2") (pintype "bidirectional"))
      (node (ref "CN13") (pin "P$2") (pinfunction "P$2_P$2") (pintype "bidirectional"))
      (node (ref "CN14") (pin "P$2") (pinfunction "P$2_P$2") (pintype "bidirectional"))
      (node (ref "CN15") (pin "P$2") (pinfunction "P$2_P$2") (pintype "bidirectional"))
      (node (ref "CN16") (pin "P$2") (pinfunction "P$2_P$2") (pintype "bidirectional"))
      (node (ref "CN18") (pin "P$2") (pinfunction "2_P$2") (pintype "passive"))
      (node (ref "CN19") (pin "P$12") (pinfunction "12_P$12") (pintype "passive"))
      (node (ref "CN2") (pin "P$2") (pinfunction "P$2_P$2") (pintype "bidirectional"))
      (node (ref "CN3") (pin "P$2") (pinfunction "P$2_P$2") (pintype "bidirectional"))
      (node (ref "CN4") (pin "P$2") (pinfunction "P$2_P$2") (pintype "bidirectional"))
      (node (ref "CN5") (pin "P$2") (pinfunction "P$2_P$2") (pintype "bidirectional"))
      (node (ref "CN6") (pin "P$2") (pinfunction "P$2_P$2") (pintype "bidirectional"))
      (node (ref "CN7") (pin "P$2") (pinfunction "P$2_P$2") (pintype "bidirectional"))
      (node (ref "CN8") (pin "P$2") (pinfunction "P$2_P$2") (pintype "bidirectional"))
      (node (ref "CN9") (pin "P$2") (pinfunction "P$2_P$2") (pintype "bidirectional"))
      (node (ref "D1") (pin "A$2") (pinfunction "A_A$2") (pintype "passive"))
      (node (ref "D10") (pin "A$2") (pinfunction "A_A$2") (pintype "passive"))
      (node (ref "D11") (pin "A$2") (pinfunction "A_A$2") (pintype "passive"))
      (node (ref "D12") (pin "A$2") (pinfunction "A_A$2") (pintype "passive"))
      (node (ref "D13") (pin "A$2") (pinfunction "A_A$2") (pintype "passive"))
      (node (ref "D14") (pin "A$2") (pinfunction "A_A$2") (pintype "passive"))
      (node (ref "D15") (pin "A$2") (pinfunction "A_A$2") (pintype "passive"))
      (node (ref "D16") (pin "A$2") (pinfunction "A_A$2") (pintype "passive"))
      (node (ref "D17") (pin "P$2") (pinfunction "C_P$2") (pintype "passive"))
      (node (ref "D18") (pin "P$2") (pinfunction "C_P$2") (pintype "passive"))
      (node (ref "D19") (pin "P$2") (pinfunction "C_P$2") (pintype "passive"))
      (node (ref "D2") (pin "A$2") (pinfunction "A_A$2") (pintype "passive"))
      (node (ref "D20") (pin "P$2") (pinfunction "C_P$2") (pintype "passive"))
      (node (ref "D21") (pin "P$2") (pinfunction "C_P$2") (pintype "passive"))
      (node (ref "D22") (pin "P$2") (pinfunction "C_P$2") (pintype "passive"))
      (node (ref "D23") (pin "P$2") (pinfunction "C_P$2") (pintype "passive"))
      (node (ref "D24") (pin "P$2") (pinfunction "C_P$2") (pintype "passive"))
      (node (ref "D25") (pin "P$2") (pinfunction "C_P$2") (pintype "passive"))
      (node (ref "D26") (pin "P$2") (pinfunction "C_P$2") (pintype "passive"))
      (node (ref "D27") (pin "P$2") (pinfunction "C_P$2") (pintype "passive"))
      (node (ref "D28") (pin "P$2") (pinfunction "C_P$2") (pintype "passive"))
      (node (ref "D29") (pin "P$2") (pinfunction "C_P$2") (pintype "passive"))
      (node (ref "D3") (pin "A$2") (pinfunction "A_A$2") (pintype "passive"))
      (node (ref "D30") (pin "P$2") (pinfunction "C_P$2") (pintype "passive"))
      (node (ref "D31") (pin "P$2") (pinfunction "C_P$2") (pintype "passive"))
      (node (ref "D32") (pin "P$2") (pinfunction "C_P$2") (pintype "passive"))
      (node (ref "D33") (pin "P$2") (pinfunction "C_P$2") (pintype "passive"))
      (node (ref "D4") (pin "A$2") (pinfunction "A_A$2") (pintype "passive"))
      (node (ref "D5") (pin "A$2") (pinfunction "A_A$2") (pintype "passive"))
      (node (ref "D6") (pin "A$2") (pinfunction "A_A$2") (pintype "passive"))
      (node (ref "D7") (pin "A$2") (pinfunction "A_A$2") (pintype "passive"))
      (node (ref "D8") (pin "A$2") (pinfunction "A_A$2") (pintype "passive"))
      (node (ref "D9") (pin "A$2") (pinfunction "A_A$2") (pintype "passive"))
      (node (ref "JMP1") (pin "1") (pinfunction "1_1") (pintype "passive"))
      (node (ref "JMP2") (pin "1") (pinfunction "1_1") (pintype "passive"))
      (node (ref "JMP3") (pin "1") (pinfunction "1_1") (pintype "passive"))
      (node (ref "JMP4") (pin "1") (pinfunction "1_1") (pintype "passive"))
      (node (ref "JMP5") (pin "1") (pinfunction "1_1") (pintype "passive"))
      (node (ref "JMP6") (pin "1") (pinfunction "1_1") (pintype "passive"))
      (node (ref "R28") (pin "1") (pinfunction "1_1") (pintype "passive"))
      (node (ref "R29") (pin "1") (pinfunction "1_1") (pintype "passive"))
      (node (ref "R30") (pin "1") (pinfunction "1_1") (pintype "passive"))
      (node (ref "S2") (pin "P$1") (pinfunction "P$1_P$1") (pintype "bidirectional"))
      (node (ref "S2") (pin "P$2") (pinfunction "P$2_P$2") (pintype "bidirectional"))
      (node (ref "U$10") (pin "1") (pinfunction "P$1_1") (pintype "bidirectional"))
      (node (ref "U$10") (pin "4") (pinfunction "P$4_4") (pintype "bidirectional"))
      (node (ref "U$12") (pin "1") (pinfunction "P$1_1") (pintype "bidirectional"))
      (node (ref "U$12") (pin "4") (pinfunction "P$4_4") (pintype "bidirectional"))
      (node (ref "U$14") (pin "1") (pinfunction "P$1_1") (pintype "bidirectional"))
      (node (ref "U$14") (pin "4") (pinfunction "P$4_4") (pintype "bidirectional"))
      (node (ref "U$16") (pin "1") (pinfunction "P$1_1") (pintype "bidirectional"))
      (node (ref "U$16") (pin "4") (pinfunction "P$4_4") (pintype "bidirectional"))
      (node (ref "U$2") (pin "1") (pinfunction "P$1_1") (pintype "bidirectional"))
      (node (ref "U$2") (pin "4") (pinfunction "P$4_4") (pintype "bidirectional"))
      (node (ref "U$4") (pin "1") (pinfunction "P$1_1") (pintype "bidirectional"))
      (node (ref "U$4") (pin "4") (pinfunction "P$4_4") (pintype "bidirectional"))
      (node (ref "U$6") (pin "1") (pinfunction "P$1_1") (pintype "bidirectional"))
      (node (ref "U$6") (pin "4") (pinfunction "P$4_4") (pintype "bidirectional"))
      (node (ref "U$8") (pin "1") (pinfunction "P$1_1") (pintype "bidirectional"))
      (node (ref "U$8") (pin "4") (pinfunction "P$4_4") (pintype "bidirectional"))
      (node (ref "U1") (pin "GND") (pinfunction "P$1_GND") (pintype "bidirectional"))
      (node (ref "U1") (pin "P$1") (pinfunction "P$1_P$1") (pintype "bidirectional"))
      (node (ref "U1") (pin "P$10") (pinfunction "P$1_P$10") (pintype "bidirectional"))
      (node (ref "U1") (pin "P$11") (pinfunction "P$1_P$11") (pintype "bidirectional"))
      (node (ref "U1") (pin "P$12") (pinfunction "P$1_P$12") (pintype "bidirectional"))
      (node (ref "U1") (pin "P$2") (pinfunction "P$1_P$2") (pintype "bidirectional"))
      (node (ref "U1") (pin "P$3") (pinfunction "P$1_P$3") (pintype "bidirectional"))
      (node (ref "U1") (pin "P$4") (pinfunction "P$1_P$4") (pintype "bidirectional"))
      (node (ref "U1") (pin "P$5") (pinfunction "P$1_P$5") (pintype "bidirectional"))
      (node (ref "U1") (pin "P$6") (pinfunction "P$1_P$6") (pintype "bidirectional"))
      (node (ref "U1") (pin "P$7") (pinfunction "P$1_P$7") (pintype "bidirectional"))
      (node (ref "U1") (pin "P$8") (pinfunction "P$1_P$8") (pintype "bidirectional"))
      (node (ref "U1") (pin "P$9") (pinfunction "P$1_P$9") (pintype "bidirectional"))
      (node (ref "U1") (pin "P1") (pinfunction "GND_P1") (pintype "power_in"))
      (node (ref "U1") (pin "P7") (pinfunction "PGND_P7") (pintype "power_in"))
      (node (ref "U10") (pin "4") (pinfunction "GND_4") (pintype "bidirectional"))
      (node (ref "U11") (pin "3") (pinfunction "GND_3") (pintype "bidirectional"))
      (node (ref "U2") (pin "2") (pinfunction "GND_2") (pintype "power_in"))
      (node (ref "U2") (pin "3") (pinfunction "VR2_3") (pintype "bidirectional"))
      (node (ref "U2") (pin "7") (pinfunction "VR1_7") (pintype "bidirectional"))
      (node (ref "U3") (pin "1") (pinfunction "GND_1") (pintype "power_in"))
      (node (ref "U4") (pin "2") (pinfunction "GND$1_2") (pintype "power_in"))
      (node (ref "U4") (pin "3") (pinfunction "GND$2_3") (pintype "power_in"))
      (node (ref "U4") (pin "5") (pinfunction "GND$3_5") (pintype "power_in"))
      (node (ref "U5") (pin "P11") (pinfunction "ADDR_P11") (pintype "input"))
      (node (ref "U5") (pin "P23") (pinfunction "VSS_P23") (pintype "power_in"))
      (node (ref "U6") (pin "GND") (pinfunction "P$1_GND") (pintype "bidirectional"))
      (node (ref "U6") (pin "P$1") (pinfunction "P$1_P$1") (pintype "bidirectional"))
      (node (ref "U6") (pin "P$10") (pinfunction "P$1_P$10") (pintype "bidirectional"))
      (node (ref "U6") (pin "P$11") (pinfunction "P$1_P$11") (pintype "bidirectional"))
      (node (ref "U6") (pin "P$12") (pinfunction "P$1_P$12") (pintype "bidirectional"))
      (node (ref "U6") (pin "P$2") (pinfunction "P$1_P$2") (pintype "bidirectional"))
      (node (ref "U6") (pin "P$3") (pinfunction "P$1_P$3") (pintype "bidirectional"))
      (node (ref "U6") (pin "P$4") (pinfunction "P$1_P$4") (pintype "bidirectional"))
      (node (ref "U6") (pin "P$5") (pinfunction "P$1_P$5") (pintype "bidirectional"))
      (node (ref "U6") (pin "P$6") (pinfunction "P$1_P$6") (pintype "bidirectional"))
      (node (ref "U6") (pin "P$7") (pinfunction "P$1_P$7") (pintype "bidirectional"))
      (node (ref "U6") (pin "P$8") (pinfunction "P$1_P$8") (pintype "bidirectional"))
      (node (ref "U6") (pin "P$9") (pinfunction "P$1_P$9") (pintype "bidirectional"))
      (node (ref "U6") (pin "P1") (pinfunction "GND_P1") (pintype "power_in"))
      (node (ref "U6") (pin "P7") (pinfunction "PGND_P7") (pintype "power_in"))
      (node (ref "U7") (pin "GND") (pinfunction "P$1_GND") (pintype "bidirectional"))
      (node (ref "U7") (pin "P$1") (pinfunction "P$1_P$1") (pintype "bidirectional"))
      (node (ref "U7") (pin "P$10") (pinfunction "P$1_P$10") (pintype "bidirectional"))
      (node (ref "U7") (pin "P$11") (pinfunction "P$1_P$11") (pintype "bidirectional"))
      (node (ref "U7") (pin "P$12") (pinfunction "P$1_P$12") (pintype "bidirectional"))
      (node (ref "U7") (pin "P$2") (pinfunction "P$1_P$2") (pintype "bidirectional"))
      (node (ref "U7") (pin "P$3") (pinfunction "P$1_P$3") (pintype "bidirectional"))
      (node (ref "U7") (pin "P$4") (pinfunction "P$1_P$4") (pintype "bidirectional"))
      (node (ref "U7") (pin "P$5") (pinfunction "P$1_P$5") (pintype "bidirectional"))
      (node (ref "U7") (pin "P$6") (pinfunction "P$1_P$6") (pintype "bidirectional"))
      (node (ref "U7") (pin "P$7") (pinfunction "P$1_P$7") (pintype "bidirectional"))
      (node (ref "U7") (pin "P$8") (pinfunction "P$1_P$8") (pintype "bidirectional"))
      (node (ref "U7") (pin "P$9") (pinfunction "P$1_P$9") (pintype "bidirectional"))
      (node (ref "U7") (pin "P1") (pinfunction "GND_P1") (pintype "power_in"))
      (node (ref "U7") (pin "P7") (pinfunction "PGND_P7") (pintype "power_in"))
      (node (ref "U8") (pin "P$7") (pinfunction "GND_P$7") (pintype "power_in"))
      (node (ref "U9") (pin "4") (pinfunction "GND_4") (pintype "bidirectional"))
    )
    (net (code "13") (name "IOUT") (class "Default")
      (node (ref "U2") (pin "5") (pinfunction "OUT$1_5") (pintype "output"))
      (node (ref "U8") (pin "P$1") (pinfunction "AIN0_P$1") (pintype "input"))
      (node (ref "U8") (pin "P$2") (pinfunction "AIN1_P$2") (pintype "input"))
    )
    (net (code "14") (name "MC1") (class "Default")
      (node (ref "U$2") (pin "2") (pinfunction "P$2_2") (pintype "bidirectional"))
      (node (ref "U5") (pin "P15") (pinfunction "GPA$0_P15") (pintype "bidirectional"))
    )
    (net (code "15") (name "MC2") (class "Default")
      (node (ref "U$2") (pin "5") (pinfunction "P$5_5") (pintype "bidirectional"))
      (node (ref "U5") (pin "P16") (pinfunction "GPA$1_P16") (pintype "bidirectional"))
    )
    (net (code "16") (name "MC3") (class "Default")
      (node (ref "U$4") (pin "2") (pinfunction "P$2_2") (pintype "bidirectional"))
      (node (ref "U5") (pin "P17") (pinfunction "GPA$2_P17") (pintype "bidirectional"))
    )
    (net (code "17") (name "MC4") (class "Default")
      (node (ref "U$4") (pin "5") (pinfunction "P$5_5") (pintype "bidirectional"))
      (node (ref "U5") (pin "P18") (pinfunction "GPA$3_P18") (pintype "bidirectional"))
    )
    (net (code "18") (name "MC5") (class "Default")
      (node (ref "U$6") (pin "2") (pinfunction "P$2_2") (pintype "bidirectional"))
      (node (ref "U5") (pin "P19") (pinfunction "GPA$4_P19") (pintype "bidirectional"))
    )
    (net (code "19") (name "MC6") (class "Default")
      (node (ref "U$6") (pin "5") (pinfunction "P$5_5") (pintype "bidirectional"))
      (node (ref "U5") (pin "P20") (pinfunction "GPA$5_P20") (pintype "bidirectional"))
    )
    (net (code "20") (name "MC7") (class "Default")
      (node (ref "U$8") (pin "2") (pinfunction "P$2_2") (pintype "bidirectional"))
      (node (ref "U5") (pin "P21") (pinfunction "GPA$6_P21") (pintype "bidirectional"))
    )
    (net (code "21") (name "MC8") (class "Default")
      (node (ref "U$8") (pin "5") (pinfunction "P$5_5") (pintype "bidirectional"))
      (node (ref "U5") (pin "P22") (pinfunction "GPA$7_P22") (pintype "bidirectional"))
    )
    (net (code "22") (name "MC9") (class "Default")
      (node (ref "U$10") (pin "2") (pinfunction "P$2_2") (pintype "bidirectional"))
      (node (ref "U5") (pin "P24") (pinfunction "GPB$0_P24") (pintype "bidirectional"))
    )
    (net (code "23") (name "MC10") (class "Default")
      (node (ref "U$10") (pin "5") (pinfunction "P$5_5") (pintype "bidirectional"))
      (node (ref "U5") (pin "P1") (pinfunction "GPB$1_P1") (pintype "bidirectional"))
    )
    (net (code "24") (name "MC11") (class "Default")
      (node (ref "U$12") (pin "2") (pinfunction "P$2_2") (pintype "bidirectional"))
      (node (ref "U5") (pin "P2") (pinfunction "GPB$2_P2") (pintype "bidirectional"))
    )
    (net (code "25") (name "MC12") (class "Default")
      (node (ref "U$12") (pin "5") (pinfunction "P$5_5") (pintype "bidirectional"))
      (node (ref "U5") (pin "P3") (pinfunction "GPB$3_P3") (pintype "bidirectional"))
    )
    (net (code "26") (name "MC13") (class "Default")
      (node (ref "U$14") (pin "2") (pinfunction "P$2_2") (pintype "bidirectional"))
      (node (ref "U5") (pin "P4") (pinfunction "GPB$4_P4") (pintype "bidirectional"))
    )
    (net (code "27") (name "MC14") (class "Default")
      (node (ref "U$14") (pin "5") (pinfunction "P$5_5") (pintype "bidirectional"))
      (node (ref "U5") (pin "P5") (pinfunction "GPB$5_P5") (pintype "bidirectional"))
    )
    (net (code "28") (name "MC15") (class "Default")
      (node (ref "U$16") (pin "2") (pinfunction "P$2_2") (pintype "bidirectional"))
      (node (ref "U5") (pin "P6") (pinfunction "GPB$6_P6") (pintype "bidirectional"))
    )
    (net (code "29") (name "MC16") (class "Default")
      (node (ref "U$16") (pin "5") (pinfunction "P$5_5") (pintype "bidirectional"))
      (node (ref "U5") (pin "P7") (pinfunction "GPB$7_P7") (pintype "bidirectional"))
    )
    (net (code "30") (name "Net-(CN18-1)") (class "Default")
      (node (ref "CN18") (pin "P$1") (pinfunction "1_P$1") (pintype "passive"))
      (node (ref "F1") (pin "P$2") (pinfunction "2_P$2") (pintype "passive"))
    )
    (net (code "31") (name "Net-(D1-C)") (class "Default")
      (node (ref "CN1") (pin "P$1") (pinfunction "P$1_P$1") (pintype "bidirectional"))
      (node (ref "D1") (pin "C$1") (pinfunction "C_C$1") (pintype "passive"))
      (node (ref "R22") (pin "1") (pinfunction "1_1") (pintype "passive"))
      (node (ref "U$1") (pin "7") (pinfunction "D$1B_7") (pintype "bidirectional"))
      (node (ref "U$1") (pin "8") (pinfunction "D$1A_8") (pintype "bidirectional"))
    )
    (net (code "32") (name "Net-(D2-C)") (class "Default")
      (node (ref "CN3") (pin "P$1") (pinfunction "P$1_P$1") (pintype "bidirectional"))
      (node (ref "D2") (pin "C$1") (pinfunction "C_C$1") (pintype "passive"))
      (node (ref "R23") (pin "2") (pinfunction "2_2") (pintype "passive"))
      (node (ref "U$1") (pin "5") (pinfunction "D$2B_5") (pintype "bidirectional"))
      (node (ref "U$1") (pin "6") (pinfunction "D$2A_6") (pintype "bidirectional"))
    )
    (net (code "33") (name "Net-(D3-C)") (class "Default")
      (node (ref "CN7") (pin "P$1") (pinfunction "P$1_P$1") (pintype "bidirectional"))
      (node (ref "D3") (pin "C$1") (pinfunction "C_C$1") (pintype "passive"))
      (node (ref "R36") (pin "1") (pinfunction "1_1") (pintype "passive"))
      (node (ref "U$7") (pin "7") (pinfunction "D$1B_7") (pintype "bidirectional"))
      (node (ref "U$7") (pin "8") (pinfunction "D$1A_8") (pintype "bidirectional"))
    )
    (net (code "34") (name "Net-(D4-C)") (class "Default")
      (node (ref "CN8") (pin "P$1") (pinfunction "P$1_P$1") (pintype "bidirectional"))
      (node (ref "D4") (pin "C$1") (pinfunction "C_C$1") (pintype "passive"))
      (node (ref "R37") (pin "2") (pinfunction "2_2") (pintype "passive"))
      (node (ref "U$7") (pin "5") (pinfunction "D$2B_5") (pintype "bidirectional"))
      (node (ref "U$7") (pin "6") (pinfunction "D$2A_6") (pintype "bidirectional"))
    )
    (net (code "35") (name "Net-(D5-C)") (class "Default")
      (node (ref "CN2") (pin "P$1") (pinfunction "P$1_P$1") (pintype "bidirectional"))
      (node (ref "D5") (pin "C$1") (pinfunction "C_C$1") (pintype "passive"))
      (node (ref "R3") (pin "1") (pinfunction "1_1") (pintype "passive"))
      (node (ref "U$3") (pin "7") (pinfunction "D$1B_7") (pintype "bidirectional"))
      (node (ref "U$3") (pin "8") (pinfunction "D$1A_8") (pintype "bidirectional"))
    )
    (net (code "36") (name "Net-(D6-C)") (class "Default")
      (node (ref "CN4") (pin "P$1") (pinfunction "P$1_P$1") (pintype "bidirectional"))
      (node (ref "D6") (pin "C$1") (pinfunction "C_C$1") (pintype "passive"))
      (node (ref "R4") (pin "2") (pinfunction "2_2") (pintype "passive"))
      (node (ref "U$3") (pin "5") (pinfunction "D$2B_5") (pintype "bidirectional"))
      (node (ref "U$3") (pin "6") (pinfunction "D$2A_6") (pintype "bidirectional"))
    )
    (net (code "37") (name "Net-(D7-C)") (class "Default")
      (node (ref "CN5") (pin "P$1") (pinfunction "P$1_P$1") (pintype "bidirectional"))
      (node (ref "D7") (pin "C$1") (pinfunction "C_C$1") (pintype "passive"))
      (node (ref "R24") (pin "1") (pinfunction "1_1") (pintype "passive"))
      (node (ref "U$5") (pin "7") (pinfunction "D$1B_7") (pintype "bidirectional"))
      (node (ref "U$5") (pin "8") (pinfunction "D$1A_8") (pintype "bidirectional"))
    )
    (net (code "38") (name "Net-(D8-C)") (class "Default")
      (node (ref "CN6") (pin "P$1") (pinfunction "P$1_P$1") (pintype "bidirectional"))
      (node (ref "D8") (pin "C$1") (pinfunction "C_C$1") (pintype "passive"))
      (node (ref "R25") (pin "2") (pinfunction "2_2") (pintype "passive"))
      (node (ref "U$5") (pin "5") (pinfunction "D$2B_5") (pintype "bidirectional"))
      (node (ref "U$5") (pin "6") (pinfunction "D$2A_6") (pintype "bidirectional"))
    )
    (net (code "39") (name "Net-(D9-C)") (class "Default")
      (node (ref "CN9") (pin "P$1") (pinfunction "P$1_P$1") (pintype "bidirectional"))
      (node (ref "D9") (pin "C$1") (pinfunction "C_C$1") (pintype "passive"))
      (node (ref "R11") (pin "1") (pinfunction "1_1") (pintype "passive"))
      (node (ref "U$9") (pin "7") (pinfunction "D$1B_7") (pintype "bidirectional"))
      (node (ref "U$9") (pin "8") (pinfunction "D$1A_8") (pintype "bidirectional"))
    )
    (net (code "40") (name "Net-(D10-C)") (class "Default")
      (node (ref "CN11") (pin "P$1") (pinfunction "P$1_P$1") (pintype "bidirectional"))
      (node (ref "D10") (pin "C$1") (pinfunction "C_C$1") (pintype "passive"))
      (node (ref "R12") (pin "2") (pinfunction "2_2") (pintype "passive"))
      (node (ref "U$9") (pin "5") (pinfunction "D$2B_5") (pintype "bidirectional"))
      (node (ref "U$9") (pin "6") (pinfunction "D$2A_6") (pintype "bidirectional"))
    )
    (net (code "41") (name "Net-(D11-C)") (class "Default")
      (node (ref "CN15") (pin "P$1") (pinfunction "P$1_P$1") (pintype "bidirectional"))
      (node (ref "D11") (pin "C$1") (pinfunction "C_C$1") (pintype "passive"))
      (node (ref "R44") (pin "1") (pinfunction "1_1") (pintype "passive"))
      (node (ref "U$15") (pin "7") (pinfunction "D$1B_7") (pintype "bidirectional"))
      (node (ref "U$15") (pin "8") (pinfunction "D$1A_8") (pintype "bidirectional"))
    )
    (net (code "42") (name "Net-(D12-C)") (class "Default")
      (node (ref "CN16") (pin "P$1") (pinfunction "P$1_P$1") (pintype "bidirectional"))
      (node (ref "D12") (pin "C$1") (pinfunction "C_C$1") (pintype "passive"))
      (node (ref "R45") (pin "2") (pinfunction "2_2") (pintype "passive"))
      (node (ref "U$15") (pin "5") (pinfunction "D$2B_5") (pintype "bidirectional"))
      (node (ref "U$15") (pin "6") (pinfunction "D$2A_6") (pintype "bidirectional"))
    )
    (net (code "43") (name "Net-(D13-C)") (class "Default")
      (node (ref "CN10") (pin "P$1") (pinfunction "P$1_P$1") (pintype "bidirectional"))
      (node (ref "D13") (pin "C$1") (pinfunction "C_C$1") (pintype "passive"))
      (node (ref "R15") (pin "1") (pinfunction "1_1") (pintype "passive"))
      (node (ref "U$11") (pin "7") (pinfunction "D$1B_7") (pintype "bidirectional"))
      (node (ref "U$11") (pin "8") (pinfunction "D$1A_8") (pintype "bidirectional"))
    )
    (net (code "44") (name "Net-(D14-C)") (class "Default")
      (node (ref "CN12") (pin "P$1") (pinfunction "P$1_P$1") (pintype "bidirectional"))
      (node (ref "D14") (pin "C$1") (pinfunction "C_C$1") (pintype "passive"))
      (node (ref "R16") (pin "2") (pinfunction "2_2") (pintype "passive"))
      (node (ref "U$11") (pin "5") (pinfunction "D$2B_5") (pintype "bidirectional"))
      (node (ref "U$11") (pin "6") (pinfunction "D$2A_6") (pintype "bidirectional"))
    )
    (net (code "45") (name "Net-(D15-C)") (class "Default")
      (node (ref "CN13") (pin "P$1") (pinfunction "P$1_P$1") (pintype "bidirectional"))
      (node (ref "D15") (pin "C$1") (pinfunction "C_C$1") (pintype "passive"))
      (node (ref "R40") (pin "1") (pinfunction "1_1") (pintype "passive"))
      (node (ref "U$13") (pin "7") (pinfunction "D$1B_7") (pintype "bidirectional"))
      (node (ref "U$13") (pin "8") (pinfunction "D$1A_8") (pintype "bidirectional"))
    )
    (net (code "46") (name "Net-(D16-C)") (class "Default")
      (node (ref "CN14") (pin "P$1") (pinfunction "P$1_P$1") (pintype "bidirectional"))
      (node (ref "D16") (pin "C$1") (pinfunction "C_C$1") (pintype "passive"))
      (node (ref "R41") (pin "2") (pinfunction "2_2") (pintype "passive"))
      (node (ref "U$13") (pin "5") (pinfunction "D$2B_5") (pintype "bidirectional"))
      (node (ref "U$13") (pin "6") (pinfunction "D$2A_6") (pintype "bidirectional"))
    )
    (net (code "47") (name "Net-(D17-A)") (class "Default")
      (node (ref "D17") (pin "P$1") (pinfunction "A_P$1") (pintype "passive"))
      (node (ref "R3") (pin "2") (pinfunction "2_2") (pintype "passive"))
    )
    (net (code "48") (name "Net-(D18-A)") (class "Default")
      (node (ref "D18") (pin "P$1") (pinfunction "A_P$1") (pintype "passive"))
      (node (ref "R4") (pin "1") (pinfunction "1_1") (pintype "passive"))
    )
    (net (code "49") (name "Net-(D19-A)") (class "Default")
      (node (ref "D19") (pin "P$1") (pinfunction "A_P$1") (pintype "passive"))
      (node (ref "R22") (pin "2") (pinfunction "2_2") (pintype "passive"))
    )
    (net (code "50") (name "Net-(D20-A)") (class "Default")
      (node (ref "D20") (pin "P$1") (pinfunction "A_P$1") (pintype "passive"))
      (node (ref "R23") (pin "1") (pinfunction "1_1") (pintype "passive"))
    )
    (net (code "51") (name "Net-(D21-A)") (class "Default")
      (node (ref "D21") (pin "P$1") (pinfunction "A_P$1") (pintype "passive"))
      (node (ref "R24") (pin "2") (pinfunction "2_2") (pintype "passive"))
    )
    (net (code "52") (name "Net-(D22-A)") (class "Default")
      (node (ref "D22") (pin "P$1") (pinfunction "A_P$1") (pintype "passive"))
      (node (ref "R25") (pin "1") (pinfunction "1_1") (pintype "passive"))
    )
    (net (code "53") (name "Net-(D23-A)") (class "Default")
      (node (ref "D23") (pin "P$1") (pinfunction "A_P$1") (pintype "passive"))
      (node (ref "R36") (pin "2") (pinfunction "2_2") (pintype "passive"))
    )
    (net (code "54") (name "Net-(D24-A)") (class "Default")
      (node (ref "D24") (pin "P$1") (pinfunction "A_P$1") (pintype "passive"))
      (node (ref "R37") (pin "1") (pinfunction "1_1") (pintype "passive"))
    )
    (net (code "55") (name "Net-(D25-A)") (class "Default")
      (node (ref "D25") (pin "P$1") (pinfunction "A_P$1") (pintype "passive"))
      (node (ref "R15") (pin "2") (pinfunction "2_2") (pintype "passive"))
    )
    (net (code "56") (name "Net-(D26-A)") (class "Default")
      (node (ref "D26") (pin "P$1") (pinfunction "A_P$1") (pintype "passive"))
      (node (ref "R16") (pin "1") (pinfunction "1_1") (pintype "passive"))
    )
    (net (code "57") (name "Net-(D27-A)") (class "Default")
      (node (ref "D27") (pin "P$1") (pinfunction "A_P$1") (pintype "passive"))
      (node (ref "R11") (pin "2") (pinfunction "2_2") (pintype "passive"))
    )
    (net (code "58") (name "Net-(D28-A)") (class "Default")
      (node (ref "D28") (pin "P$1") (pinfunction "A_P$1") (pintype "passive"))
      (node (ref "R12") (pin "1") (pinfunction "1_1") (pintype "passive"))
    )
    (net (code "59") (name "Net-(D29-A)") (class "Default")
      (node (ref "D29") (pin "P$1") (pinfunction "A_P$1") (pintype "passive"))
      (node (ref "R40") (pin "2") (pinfunction "2_2") (pintype "passive"))
    )
    (net (code "60") (name "Net-(D30-A)") (class "Default")
      (node (ref "D30") (pin "P$1") (pinfunction "A_P$1") (pintype "passive"))
      (node (ref "R41") (pin "1") (pinfunction "1_1") (pintype "passive"))
    )
    (net (code "61") (name "Net-(D31-A)") (class "Default")
      (node (ref "D31") (pin "P$1") (pinfunction "A_P$1") (pintype "passive"))
      (node (ref "R44") (pin "2") (pinfunction "2_2") (pintype "passive"))
    )
    (net (code "62") (name "Net-(D32-A)") (class "Default")
      (node (ref "D32") (pin "P$1") (pinfunction "A_P$1") (pintype "passive"))
      (node (ref "R45") (pin "1") (pinfunction "1_1") (pintype "passive"))
    )
    (net (code "63") (name "Net-(D33-A)") (class "Default")
      (node (ref "D33") (pin "P$1") (pinfunction "A_P$1") (pintype "passive"))
      (node (ref "R34") (pin "1") (pinfunction "1_1") (pintype "passive"))
    )
    (net (code "64") (name "Net-(U$1-G$1)") (class "Default")
      (node (ref "D34") (pin "C") (pinfunction "C_C") (pintype "passive"))
      (node (ref "R20") (pin "1") (pinfunction "1_1") (pintype "passive"))
      (node (ref "U$1") (pin "2") (pinfunction "G$1_2") (pintype "bidirectional"))
    )
    (net (code "65") (name "Net-(U$1-G$2)") (class "Default")
      (node (ref "D35") (pin "C") (pinfunction "C_C") (pintype "passive"))
      (node (ref "R21") (pin "1") (pinfunction "1_1") (pintype "passive"))
      (node (ref "U$1") (pin "4") (pinfunction "G$2_4") (pintype "bidirectional"))
    )
    (net (code "66") (name "Net-(U$2-P$3)") (class "Default")
      (node (ref "D35") (pin "A") (pinfunction "A_A") (pintype "passive"))
      (node (ref "U$2") (pin "3") (pinfunction "P$3_3") (pintype "bidirectional"))
    )
    (net (code "67") (name "Net-(U$2-P$6)") (class "Default")
      (node (ref "D34") (pin "A") (pinfunction "A_A") (pintype "passive"))
      (node (ref "U$2") (pin "6") (pinfunction "P$6_6") (pintype "bidirectional"))
    )
    (net (code "68") (name "Net-(U$3-G$1)") (class "Default")
      (node (ref "D36") (pin "C") (pinfunction "C_C") (pintype "passive"))
      (node (ref "R1") (pin "1") (pinfunction "1_1") (pintype "passive"))
      (node (ref "U$3") (pin "2") (pinfunction "G$1_2") (pintype "bidirectional"))
    )
    (net (code "69") (name "Net-(U$3-G$2)") (class "Default")
      (node (ref "D37") (pin "C") (pinfunction "C_C") (pintype "passive"))
      (node (ref "R2") (pin "1") (pinfunction "1_1") (pintype "passive"))
      (node (ref "U$3") (pin "4") (pinfunction "G$2_4") (pintype "bidirectional"))
    )
    (net (code "70") (name "Net-(U$4-P$3)") (class "Default")
      (node (ref "D37") (pin "A") (pinfunction "A_A") (pintype "passive"))
      (node (ref "U$4") (pin "3") (pinfunction "P$3_3") (pintype "bidirectional"))
    )
    (net (code "71") (name "Net-(U$4-P$6)") (class "Default")
      (node (ref "D36") (pin "A") (pinfunction "A_A") (pintype "passive"))
      (node (ref "U$4") (pin "6") (pinfunction "P$6_6") (pintype "bidirectional"))
    )
    (net (code "72") (name "Net-(U$5-G$1)") (class "Default")
      (node (ref "D38") (pin "C") (pinfunction "C_C") (pintype "passive"))
      (node (ref "R5") (pin "1") (pinfunction "1_1") (pintype "passive"))
      (node (ref "U$5") (pin "2") (pinfunction "G$1_2") (pintype "bidirectional"))
    )
    (net (code "73") (name "Net-(U$5-G$2)") (class "Default")
      (node (ref "D39") (pin "C") (pinfunction "C_C") (pintype "passive"))
      (node (ref "R6") (pin "1") (pinfunction "1_1") (pintype "passive"))
      (node (ref "U$5") (pin "4") (pinfunction "G$2_4") (pintype "bidirectional"))
    )
    (net (code "74") (name "Net-(U$6-P$3)") (class "Default")
      (node (ref "D39") (pin "A") (pinfunction "A_A") (pintype "passive"))
      (node (ref "U$6") (pin "3") (pinfunction "P$3_3") (pintype "bidirectional"))
    )
    (net (code "75") (name "Net-(U$6-P$6)") (class "Default")
      (node (ref "D38") (pin "A") (pinfunction "A_A") (pintype "passive"))
      (node (ref "U$6") (pin "6") (pinfunction "P$6_6") (pintype "bidirectional"))
    )
    (net (code "76") (name "Net-(U$7-G$1)") (class "Default")
      (node (ref "D40") (pin "C") (pinfunction "C_C") (pintype "passive"))
      (node (ref "R7") (pin "1") (pinfunction "1_1") (pintype "passive"))
      (node (ref "U$7") (pin "2") (pinfunction "G$1_2") (pintype "bidirectional"))
    )
    (net (code "77") (name "Net-(U$7-G$2)") (class "Default")
      (node (ref "D41") (pin "C") (pinfunction "C_C") (pintype "passive"))
      (node (ref "R8") (pin "1") (pinfunction "1_1") (pintype "passive"))
      (node (ref "U$7") (pin "4") (pinfunction "G$2_4") (pintype "bidirectional"))
    )
    (net (code "78") (name "Net-(U$8-P$3)") (class "Default")
      (node (ref "D41") (pin "A") (pinfunction "A_A") (pintype "passive"))
      (node (ref "U$8") (pin "3") (pinfunction "P$3_3") (pintype "bidirectional"))
    )
    (net (code "79") (name "Net-(U$8-P$6)") (class "Default")
      (node (ref "D40") (pin "A") (pinfunction "A_A") (pintype "passive"))
      (node (ref "U$8") (pin "6") (pinfunction "P$6_6") (pintype "bidirectional"))
    )
    (net (code "80") (name "Net-(U$9-G$1)") (class "Default")
      (node (ref "D42") (pin "C") (pinfunction "C_C") (pintype "passive"))
      (node (ref "R9") (pin "1") (pinfunction "1_1") (pintype "passive"))
      (node (ref "U$9") (pin "2") (pinfunction "G$1_2") (pintype "bidirectional"))
    )
    (net (code "81") (name "Net-(U$9-G$2)") (class "Default")
      (node (ref "D43") (pin "C") (pinfunction "C_C") (pintype "passive"))
      (node (ref "R10") (pin "1") (pinfunction "1_1") (pintype "passive"))
      (node (ref "U$9") (pin "4") (pinfunction "G$2_4") (pintype "bidirectional"))
    )
    (net (code "82") (name "Net-(U$10-P$3)") (class "Default")
      (node (ref "D43") (pin "A") (pinfunction "A_A") (pintype "passive"))
      (node (ref "U$10") (pin "3") (pinfunction "P$3_3") (pintype "bidirectional"))
    )
    (net (code "83") (name "Net-(U$10-P$6)") (class "Default")
      (node (ref "D42") (pin "A") (pinfunction "A_A") (pintype "passive"))
      (node (ref "U$10") (pin "6") (pinfunction "P$6_6") (pintype "bidirectional"))
    )
    (net (code "84") (name "Net-(U$11-G$1)") (class "Default")
      (node (ref "D44") (pin "C") (pinfunction "C_C") (pintype "passive"))
      (node (ref "R13") (pin "1") (pinfunction "1_1") (pintype "passive"))
      (node (ref "U$11") (pin "2") (pinfunction "G$1_2") (pintype "bidirectional"))
    )
    (net (code "85") (name "Net-(U$11-G$2)") (class "Default")
      (node (ref "D45") (pin "C") (pinfunction "C_C") (pintype "passive"))
      (node (ref "R14") (pin "1") (pinfunction "1_1") (pintype "passive"))
      (node (ref "U$11") (pin "4") (pinfunction "G$2_4") (pintype "bidirectional"))
    )
    (net (code "86") (name "Net-(U$12-P$3)") (class "Default")
      (node (ref "D45") (pin "A") (pinfunction "A_A") (pintype "passive"))
      (node (ref "U$12") (pin "3") (pinfunction "P$3_3") (pintype "bidirectional"))
    )
    (net (code "87") (name "Net-(U$12-P$6)") (class "Default")
      (node (ref "D44") (pin "A") (pinfunction "A_A") (pintype "passive"))
      (node (ref "U$12") (pin "6") (pinfunction "P$6_6") (pintype "bidirectional"))
    )
    (net (code "88") (name "Net-(U$13-G$1)") (class "Default")
      (node (ref "D46") (pin "C") (pinfunction "C_C") (pintype "passive"))
      (node (ref "R38") (pin "1") (pinfunction "1_1") (pintype "passive"))
      (node (ref "U$13") (pin "2") (pinfunction "G$1_2") (pintype "bidirectional"))
    )
    (net (code "89") (name "Net-(U$13-G$2)") (class "Default")
      (node (ref "D47") (pin "C") (pinfunction "C_C") (pintype "passive"))
      (node (ref "R39") (pin "1") (pinfunction "1_1") (pintype "passive"))
      (node (ref "U$13") (pin "4") (pinfunction "G$2_4") (pintype "bidirectional"))
    )
    (net (code "90") (name "Net-(U$14-P$3)") (class "Default")
      (node (ref "D47") (pin "A") (pinfunction "A_A") (pintype "passive"))
      (node (ref "U$14") (pin "3") (pinfunction "P$3_3") (pintype "bidirectional"))
    )
    (net (code "91") (name "Net-(U$14-P$6)") (class "Default")
      (node (ref "D46") (pin "A") (pinfunction "A_A") (pintype "passive"))
      (node (ref "U$14") (pin "6") (pinfunction "P$6_6") (pintype "bidirectional"))
    )
    (net (code "92") (name "Net-(U$15-G$1)") (class "Default")
      (node (ref "D48") (pin "C") (pinfunction "C_C") (pintype "passive"))
      (node (ref "R42") (pin "1") (pinfunction "1_1") (pintype "passive"))
      (node (ref "U$15") (pin "2") (pinfunction "G$1_2") (pintype "bidirectional"))
    )
    (net (code "93") (name "Net-(U$15-G$2)") (class "Default")
      (node (ref "D49") (pin "C") (pinfunction "C_C") (pintype "passive"))
      (node (ref "R43") (pin "1") (pinfunction "1_1") (pintype "passive"))
      (node (ref "U$15") (pin "4") (pinfunction "G$2_4") (pintype "bidirectional"))
    )
    (net (code "94") (name "Net-(U$16-P$3)") (class "Default")
      (node (ref "D49") (pin "A") (pinfunction "A_A") (pintype "passive"))
      (node (ref "U$16") (pin "3") (pinfunction "P$3_3") (pintype "bidirectional"))
    )
    (net (code "95") (name "Net-(U$16-P$6)") (class "Default")
      (node (ref "D48") (pin "A") (pinfunction "A_A") (pintype "passive"))
      (node (ref "U$16") (pin "6") (pinfunction "P$6_6") (pintype "bidirectional"))
    )
    (net (code "96") (name "Net-(U1-ILIM)") (class "Default")
      (node (ref "R29") (pin "2") (pinfunction "2_2") (pintype "passive"))
      (node (ref "U1") (pin "P4") (pinfunction "ILIM_P4") (pintype "input"))
    )
    (net (code "97") (name "Net-(U1-OUT1)") (class "Default")
      (node (ref "CN17") (pin "P$1") (pinfunction "P$1_P$1") (pintype "bidirectional"))
      (node (ref "U1") (pin "P6") (pinfunction "OUT1_P6") (pintype "output"))
    )
    (net (code "98") (name "Net-(U1-OUT2)") (class "Default")
      (node (ref "CN17") (pin "P$2") (pinfunction "P$2_P$2") (pintype "bidirectional"))
      (node (ref "U1") (pin "P8") (pinfunction "OUT2_P8") (pintype "output"))
    )
    (net (code "99") (name "Net-(U3-DRF)") (class "Default")
      (node (ref "C8") (pin "1") (pinfunction "1_1") (pintype "passive"))
      (node (ref "R31") (pin "1") (pinfunction "1_1") (pintype "passive"))
      (node (ref "U3") (pin "7") (pinfunction "DRF_7") (pintype "power_in"))
      (node (ref "U3") (pin "8") (pinfunction "GRF_8") (pintype "power_in"))
    )
    (net (code "100") (name "Net-(U6-ILIM)") (class "Default")
      (node (ref "R30") (pin "2") (pinfunction "2_2") (pintype "passive"))
      (node (ref "U6") (pin "P4") (pinfunction "ILIM_P4") (pintype "input"))
    )
    (net (code "101") (name "Net-(U6-OUT1)") (class "Default")
      (node (ref "CN20") (pin "P$1") (pinfunction "P$1_P$1") (pintype "bidirectional"))
      (node (ref "U6") (pin "P6") (pinfunction "OUT1_P6") (pintype "output"))
    )
    (net (code "102") (name "Net-(U6-OUT2)") (class "Default")
      (node (ref "CN20") (pin "P$2") (pinfunction "P$2_P$2") (pintype "bidirectional"))
      (node (ref "U6") (pin "P8") (pinfunction "OUT2_P8") (pintype "output"))
    )
    (net (code "103") (name "Net-(U7-ILIM)") (class "Default")
      (node (ref "R28") (pin "2") (pinfunction "2_2") (pintype "passive"))
      (node (ref "U7") (pin "P4") (pinfunction "ILIM_P4") (pintype "input"))
    )
    (net (code "104") (name "Net-(U7-OUT1)") (class "Default")
      (node (ref "CN21") (pin "P$1") (pinfunction "P$1_P$1") (pintype "bidirectional"))
      (node (ref "U7") (pin "P6") (pinfunction "OUT1_P6") (pintype "output"))
    )
    (net (code "105") (name "Net-(U7-OUT2)") (class "Default")
      (node (ref "CN21") (pin "P$2") (pinfunction "P$2_P$2") (pintype "bidirectional"))
      (node (ref "U7") (pin "P8") (pinfunction "OUT2_P8") (pintype "output"))
    )
    (net (code "106") (name "Net-(U9-A0)") (class "Default")
      (node (ref "JMP1") (pin "2") (pinfunction "2_2") (pintype "passive"))
      (node (ref "U9") (pin "7") (pinfunction "A0_7") (pintype "bidirectional"))
    )
    (net (code "107") (name "Net-(U9-A1)") (class "Default")
      (node (ref "JMP2") (pin "2") (pinfunction "2_2") (pintype "passive"))
      (node (ref "U9") (pin "6") (pinfunction "A1_6") (pintype "bidirectional"))
    )
    (net (code "108") (name "Net-(U9-A2)") (class "Default")
      (node (ref "JMP3") (pin "2") (pinfunction "2_2") (pintype "passive"))
      (node (ref "U9") (pin "5") (pinfunction "A2_5") (pintype "bidirectional"))
    )
    (net (code "109") (name "Net-(U9-VDD)") (class "Default")
      (node (ref "C19") (pin "1") (pinfunction "1_1") (pintype "passive"))
      (node (ref "JMP1") (pin "3") (pinfunction "3_3") (pintype "passive"))
      (node (ref "JMP2") (pin "3") (pinfunction "3_3") (pintype "passive"))
      (node (ref "JMP3") (pin "3") (pinfunction "3_3") (pintype "passive"))
      (node (ref "R26") (pin "1") (pinfunction "1_1") (pintype "passive"))
      (node (ref "U9") (pin "8") (pinfunction "VDD_8") (pintype "bidirectional"))
    )
    (net (code "110") (name "Net-(U10-A0)") (class "Default")
      (node (ref "JMP4") (pin "2") (pinfunction "2_2") (pintype "passive"))
      (node (ref "U10") (pin "7") (pinfunction "A0_7") (pintype "bidirectional"))
    )
    (net (code "111") (name "Net-(U10-A1)") (class "Default")
      (node (ref "JMP5") (pin "2") (pinfunction "2_2") (pintype "passive"))
      (node (ref "U10") (pin "6") (pinfunction "A1_6") (pintype "bidirectional"))
    )
    (net (code "112") (name "Net-(U10-A2)") (class "Default")
      (node (ref "JMP6") (pin "2") (pinfunction "2_2") (pintype "passive"))
      (node (ref "U10") (pin "5") (pinfunction "A2_5") (pintype "bidirectional"))
    )
    (net (code "113") (name "Net-(U10-VDD)") (class "Default")
      (node (ref "C20") (pin "1") (pinfunction "1_1") (pintype "passive"))
      (node (ref "JMP4") (pin "3") (pinfunction "3_3") (pintype "passive"))
      (node (ref "JMP5") (pin "3") (pinfunction "3_3") (pintype "passive"))
      (node (ref "JMP6") (pin "3") (pinfunction "3_3") (pintype "passive"))
      (node (ref "R27") (pin "1") (pinfunction "1_1") (pintype "passive"))
      (node (ref "U10") (pin "8") (pinfunction "VDD_8") (pintype "bidirectional"))
    )
    (net (code "114") (name "RESET") (class "Default")
      (node (ref "R35") (pin "1") (pinfunction "1_1") (pintype "passive"))
      (node (ref "S2") (pin "P$3") (pinfunction "P$3_P$3") (pintype "bidirectional"))
      (node (ref "S2") (pin "P$4") (pinfunction "P$4_P$4") (pintype "bidirectional"))
      (node (ref "U5") (pin "P12") (pinfunction "RESET_P12") (pintype "input"))
    )
    (net (code "115") (name "SCL3.3") (class "Default")
      (node (ref "CN19") (pin "P$2") (pinfunction "2_P$2") (pintype "passive"))
      (node (ref "R17") (pin "1") (pinfunction "1_1") (pintype "passive"))
      (node (ref "U3") (pin "3") (pinfunction "S1_3") (pintype "bidirectional"))
    )
    (net (code "116") (name "SCL5") (class "Default")
      (node (ref "R32") (pin "1") (pinfunction "1_1") (pintype "passive"))
      (node (ref "U10") (pin "2") (pinfunction "SCL_2") (pintype "bidirectional"))
      (node (ref "U3") (pin "6") (pinfunction "D1_6") (pintype "bidirectional"))
      (node (ref "U5") (pin "P9") (pinfunction "SCL_P9") (pintype "input"))
      (node (ref "U8") (pin "P$5") (pinfunction "SCL_P$5") (pintype "bidirectional"))
      (node (ref "U9") (pin "2") (pinfunction "SCL_2") (pintype "bidirectional"))
    )
    (net (code "117") (name "SDA3.3") (class "Default")
      (node (ref "CN19") (pin "P$1") (pinfunction "1_P$1") (pintype "passive"))
      (node (ref "R19") (pin "1") (pinfunction "1_1") (pintype "passive"))
      (node (ref "U3") (pin "4") (pinfunction "S2_4") (pintype "bidirectional"))
    )
    (net (code "118") (name "SDA5") (class "Default")
      (node (ref "R33") (pin "1") (pinfunction "1_1") (pintype "passive"))
      (node (ref "U10") (pin "1") (pinfunction "SDA_1") (pintype "bidirectional"))
      (node (ref "U3") (pin "5") (pinfunction "D2_5") (pintype "bidirectional"))
      (node (ref "U5") (pin "P10") (pinfunction "SDA_P10") (pintype "bidirectional"))
      (node (ref "U8") (pin "P$6") (pinfunction "SDA_P$6") (pintype "bidirectional"))
      (node (ref "U9") (pin "1") (pinfunction "SDA_1") (pintype "bidirectional"))
    )
    (net (code "119") (name "unconnected-(U2-NC-Pad4)") (class "Default")
      (node (ref "U2") (pin "4") (pinfunction "NC_4") (pintype "no_connect"))
    )
    (net (code "120") (name "unconnected-(U5-INTA-PadP14)") (class "Default")
      (node (ref "U5") (pin "P14") (pinfunction "INTA_P14") (pintype "output"))
    )
    (net (code "121") (name "unconnected-(U5-INTB-PadP13)") (class "Default")
      (node (ref "U5") (pin "P13") (pinfunction "INTB_P13") (pintype "output"))
    )
    (net (code "122") (name "unconnected-(U8-NC-PadP$3)") (class "Default")
      (node (ref "U8") (pin "P$3") (pinfunction "NC_P$3") (pintype "no_connect"))
    )
    (net (code "123") (name "unconnected-(U9-ALERT-Pad3)") (class "Default")
      (node (ref "U9") (pin "3") (pinfunction "ALERT_3") (pintype "bidirectional"))
    )
    (net (code "124") (name "unconnected-(U10-ALERT-Pad3)") (class "Default")
      (node (ref "U10") (pin "3") (pinfunction "ALERT_3") (pintype "bidirectional"))
    )
  )
)
